# MotorBoard.net
KiCad netlist of a schematic drawn in EAGLE
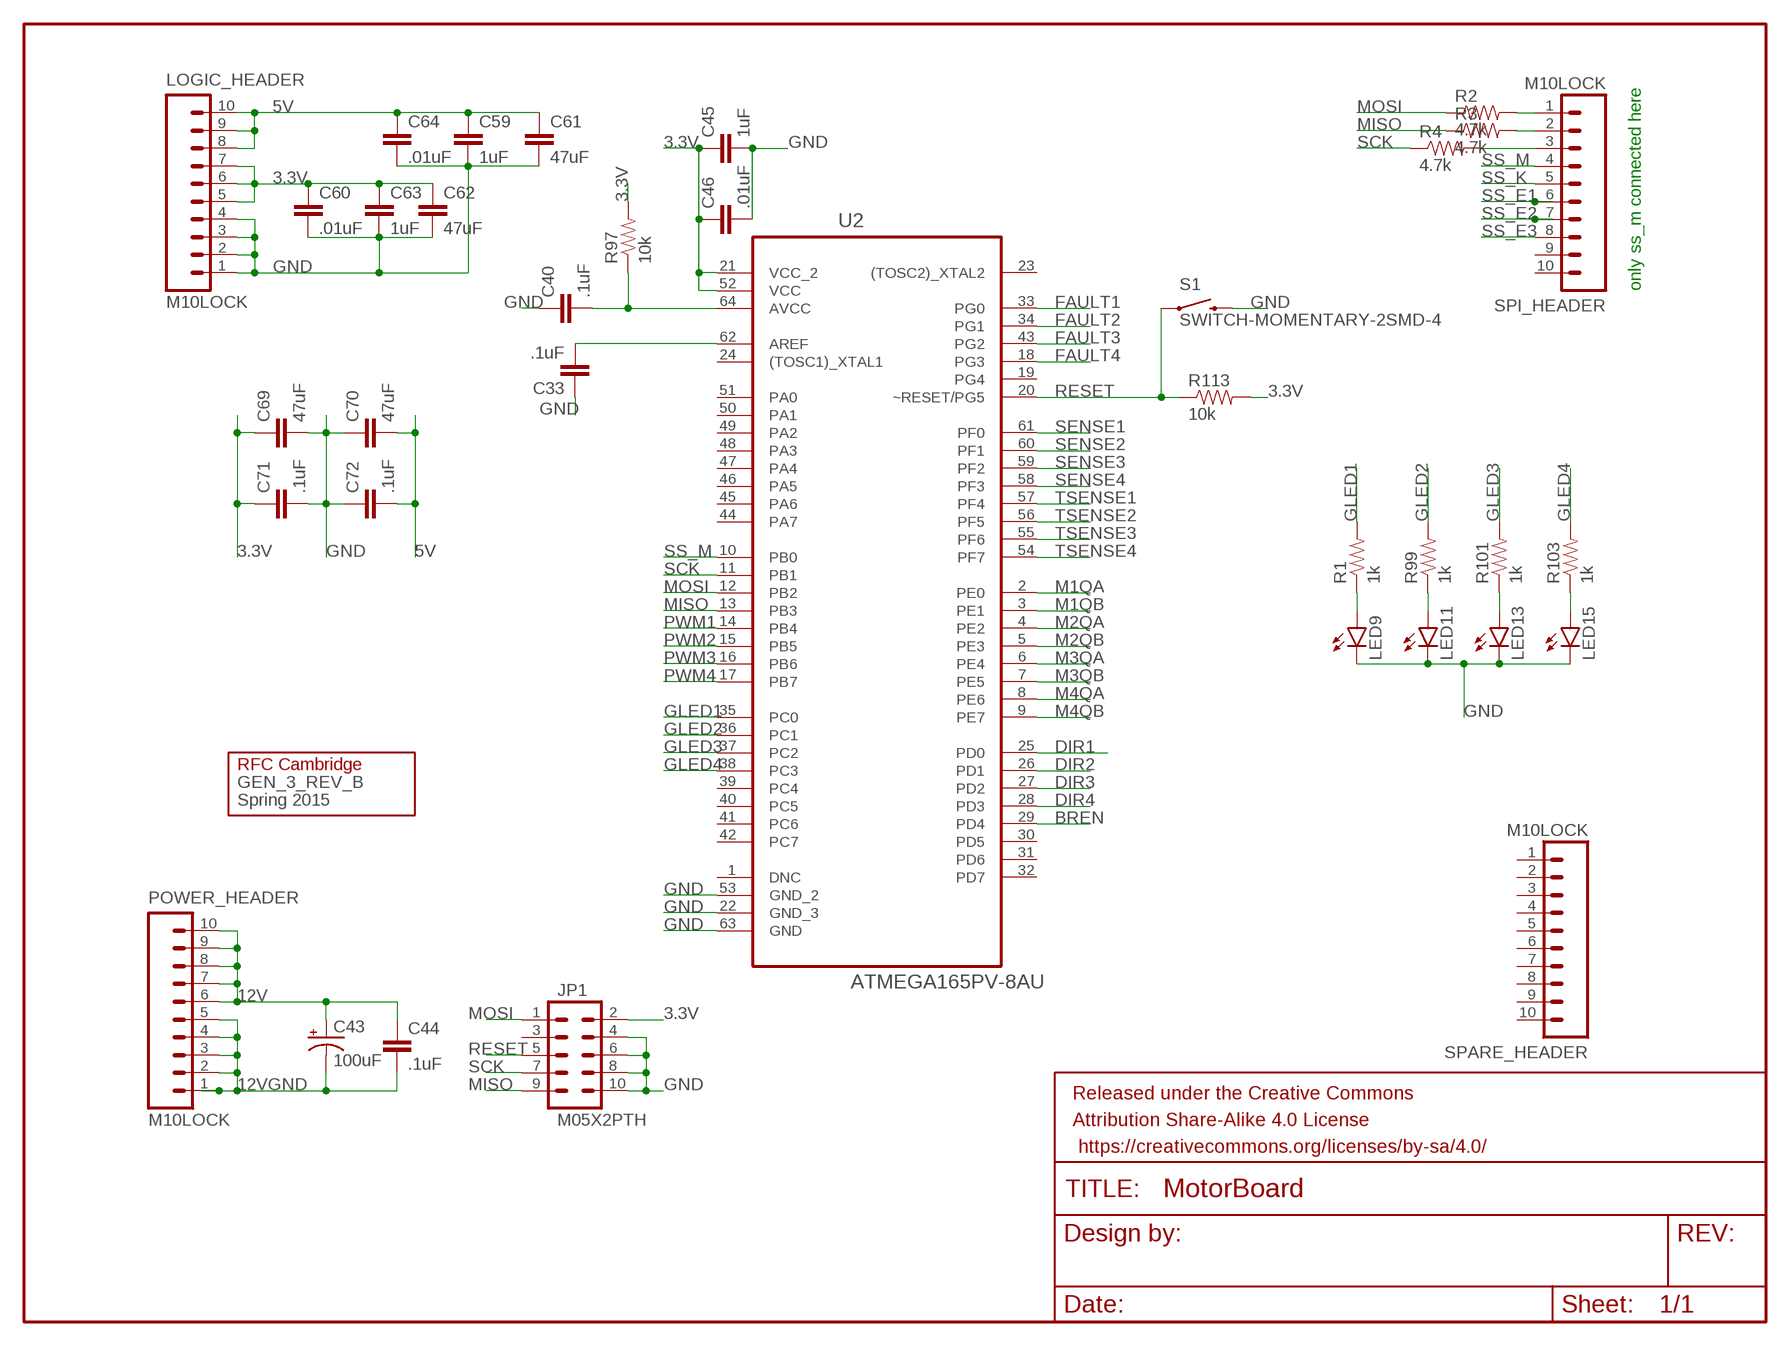
[diagram p0: schematic, sheet 1, part 1 of 2]
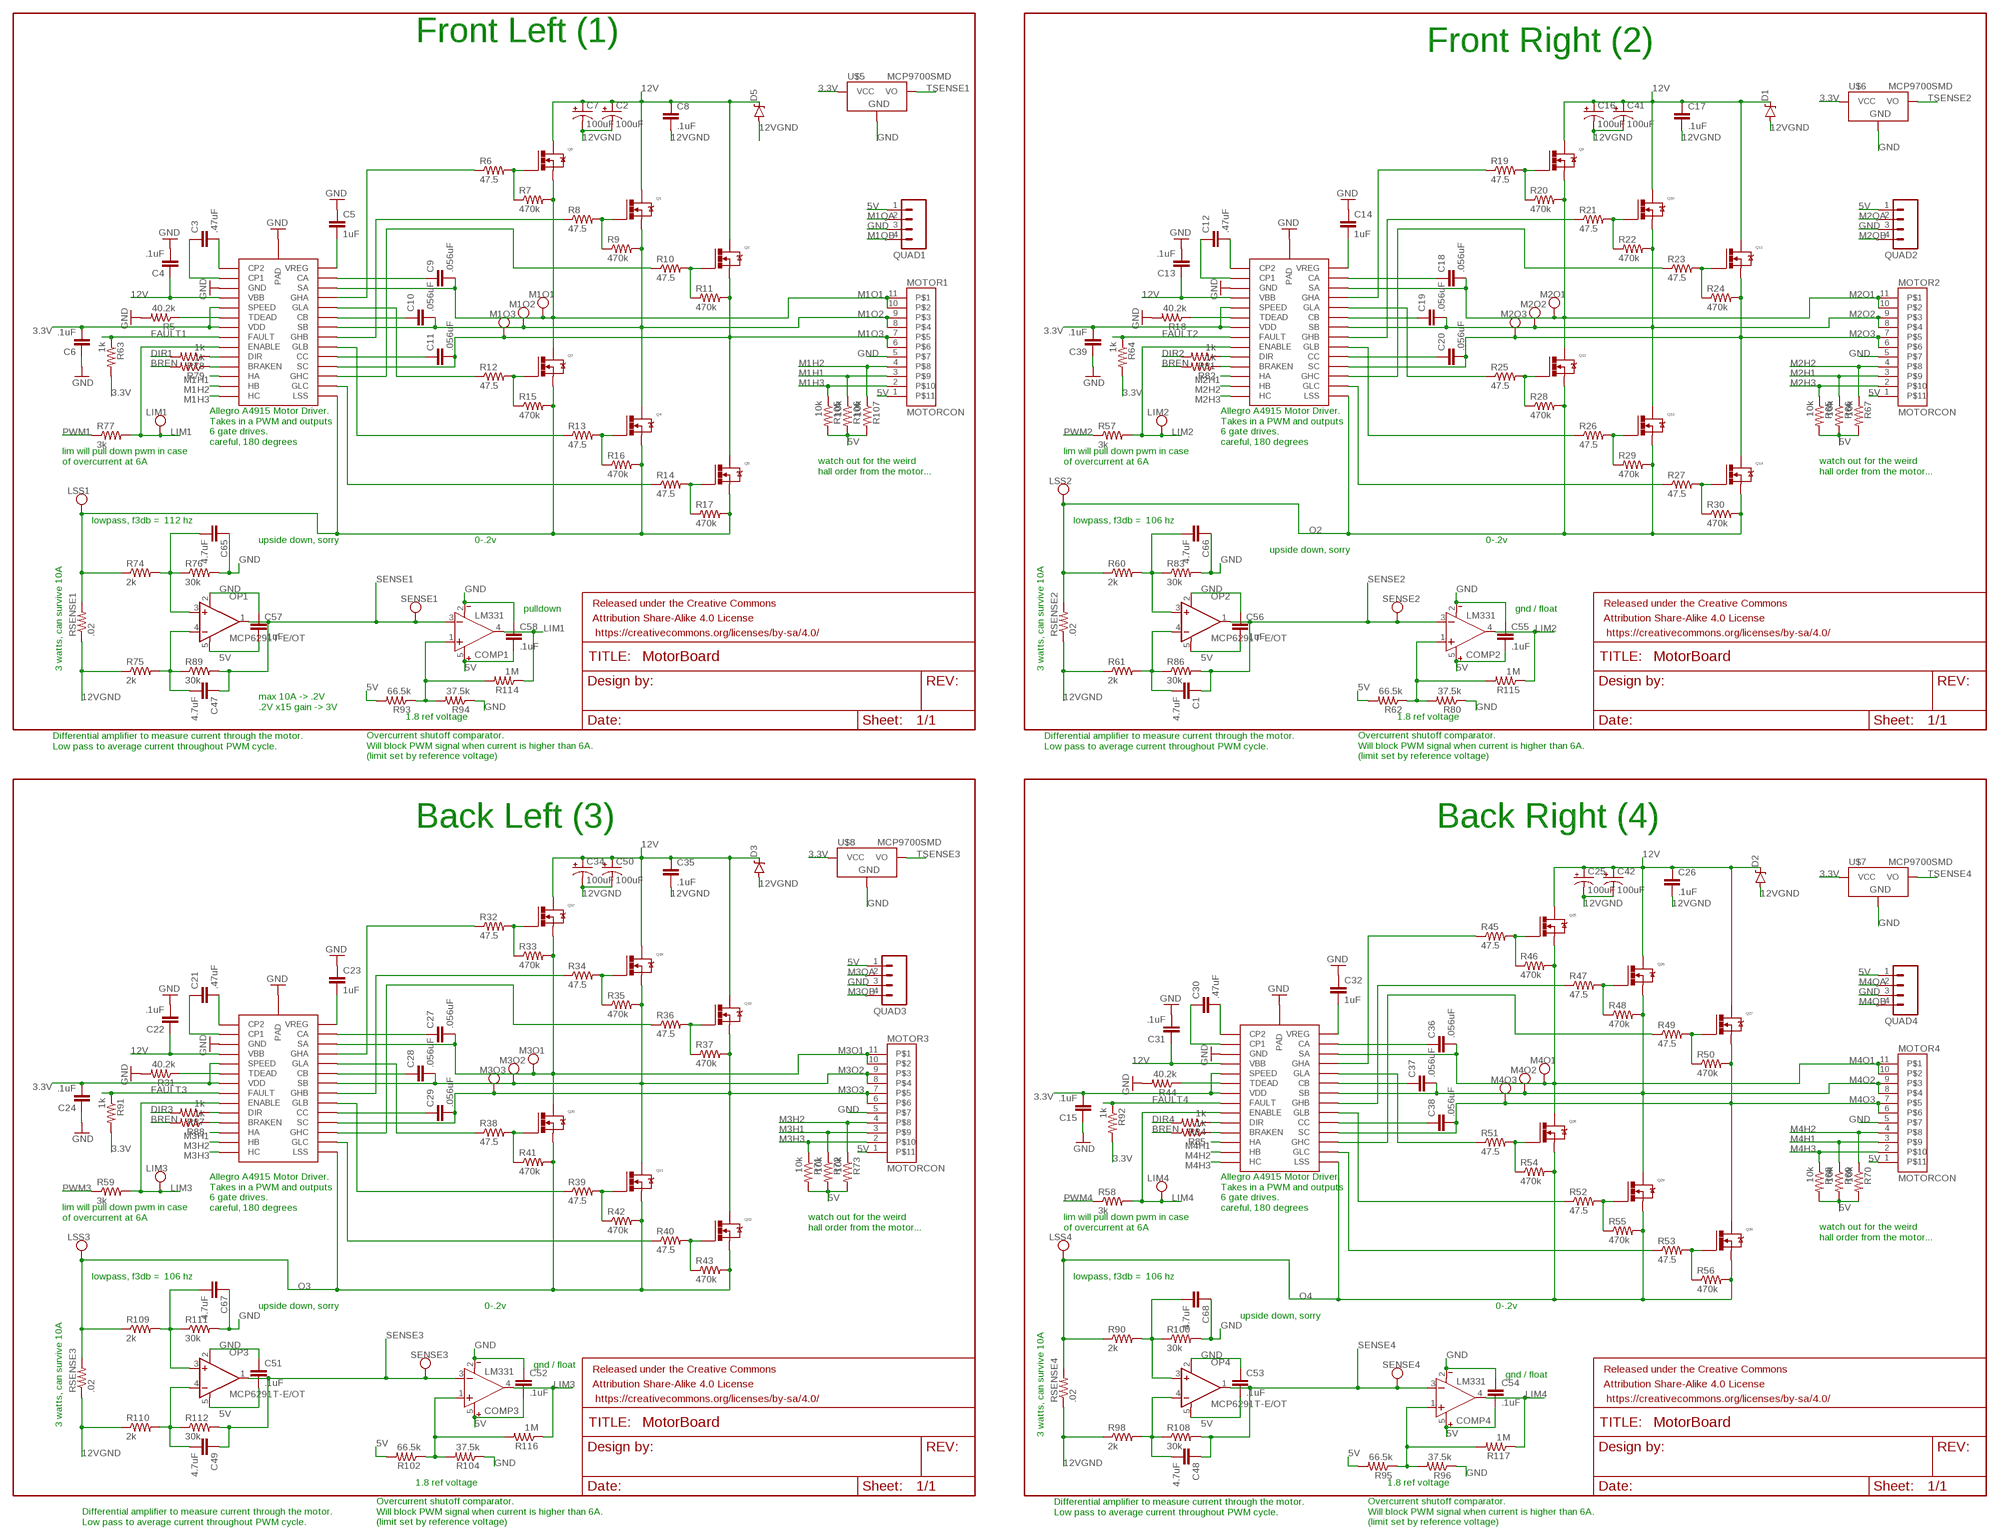
[diagram p1: schematic, sheet 1, part 2 of 2]

(export (version "E")
  (design (tool "Eeschema 10.0.6"))
  (components
    (comp (ref "C1")
      (value "4.7uF")
      (footprint "eagle-import:0805")
      (libsource (lib "eagle-import") (part "SparkFun-Passives_CAP0805"))
    )
    (comp (ref "C2")
      (value "100uF")
      (footprint "eagle-import:PANASONIC_D")
      (libsource (lib "eagle-import") (part "CAP-POLAR"))
    )
    (comp (ref "C3")
      (value ".47uF")
      (footprint "eagle-import:0805")
      (libsource (lib "eagle-import") (part "SparkFun-Passives_CAP0805"))
    )
    (comp (ref "C4")
      (value ".1uF")
      (footprint "eagle-import:0805")
      (libsource (lib "eagle-import") (part "SparkFun-Passives_CAP0805"))
    )
    (comp (ref "C5")
      (value "1uF")
      (footprint "eagle-import:0805")
      (libsource (lib "eagle-import") (part "SparkFun-Passives_CAP0805"))
    )
    (comp (ref "C6")
      (value ".1uF")
      (footprint "eagle-import:0805")
      (libsource (lib "eagle-import") (part "SparkFun-Passives_CAP0805"))
    )
    (comp (ref "C7")
      (value "100uF")
      (footprint "eagle-import:PANASONIC_D")
      (libsource (lib "eagle-import") (part "CAP-POLAR"))
    )
    (comp (ref "C8")
      (value ".1uF")
      (footprint "eagle-import:0805")
      (libsource (lib "eagle-import") (part "SparkFun-Passives_CAP0805"))
    )
    (comp (ref "C9")
      (value ".056uF")
      (footprint "eagle-import:0805")
      (libsource (lib "eagle-import") (part "SparkFun-Passives_CAP0805"))
    )
    (comp (ref "C10")
      (value ".056uF")
      (footprint "eagle-import:0805")
      (libsource (lib "eagle-import") (part "SparkFun-Passives_CAP0805"))
    )
    (comp (ref "C11")
      (value ".056uF")
      (footprint "eagle-import:0805")
      (libsource (lib "eagle-import") (part "SparkFun-Passives_CAP0805"))
    )
    (comp (ref "C12")
      (value ".47uF")
      (footprint "eagle-import:0805")
      (libsource (lib "eagle-import") (part "SparkFun-Passives_CAP0805"))
    )
    (comp (ref "C13")
      (value ".1uF")
      (footprint "eagle-import:0805")
      (libsource (lib "eagle-import") (part "SparkFun-Passives_CAP0805"))
    )
    (comp (ref "C14")
      (value "1uF")
      (footprint "eagle-import:0805")
      (libsource (lib "eagle-import") (part "SparkFun-Passives_CAP0805"))
    )
    (comp (ref "C15")
      (value ".1uF")
      (footprint "eagle-import:0805")
      (libsource (lib "eagle-import") (part "SparkFun-Passives_CAP0805"))
    )
    (comp (ref "C16")
      (value "100uF")
      (footprint "eagle-import:PANASONIC_D")
      (libsource (lib "eagle-import") (part "CAP-POLAR"))
    )
    (comp (ref "C17")
      (value ".1uF")
      (footprint "eagle-import:0805")
      (libsource (lib "eagle-import") (part "SparkFun-Passives_CAP0805"))
    )
    (comp (ref "C18")
      (value ".056uF")
      (footprint "eagle-import:0805")
      (libsource (lib "eagle-import") (part "SparkFun-Passives_CAP0805"))
    )
    (comp (ref "C19")
      (value ".056uF")
      (footprint "eagle-import:0805")
      (libsource (lib "eagle-import") (part "SparkFun-Passives_CAP0805"))
    )
    (comp (ref "C20")
      (value ".056uF")
      (footprint "eagle-import:0805")
      (libsource (lib "eagle-import") (part "SparkFun-Passives_CAP0805"))
    )
    (comp (ref "C21")
      (value ".47uF")
      (footprint "eagle-import:0805")
      (libsource (lib "eagle-import") (part "SparkFun-Passives_CAP0805"))
    )
    (comp (ref "C22")
      (value ".1uF")
      (footprint "eagle-import:0805")
      (libsource (lib "eagle-import") (part "SparkFun-Passives_CAP0805"))
    )
    (comp (ref "C23")
      (value "1uF")
      (footprint "eagle-import:0805")
      (libsource (lib "eagle-import") (part "SparkFun-Passives_CAP0805"))
    )
    (comp (ref "C24")
      (value ".1uF")
      (footprint "eagle-import:0805")
      (libsource (lib "eagle-import") (part "SparkFun-Passives_CAP0805"))
    )
    (comp (ref "C25")
      (value "100uF")
      (footprint "eagle-import:PANASONIC_D")
      (libsource (lib "eagle-import") (part "CAP-POLAR"))
    )
    (comp (ref "C26")
      (value ".1uF")
      (footprint "eagle-import:0805")
      (libsource (lib "eagle-import") (part "SparkFun-Passives_CAP0805"))
    )
    (comp (ref "C27")
      (value ".056uF")
      (footprint "eagle-import:0805")
      (libsource (lib "eagle-import") (part "SparkFun-Passives_CAP0805"))
    )
    (comp (ref "C28")
      (value ".056uF")
      (footprint "eagle-import:0805")
      (libsource (lib "eagle-import") (part "SparkFun-Passives_CAP0805"))
    )
    (comp (ref "C29")
      (value ".056uF")
      (footprint "eagle-import:0805")
      (libsource (lib "eagle-import") (part "SparkFun-Passives_CAP0805"))
    )
    (comp (ref "C30")
      (value ".47uF")
      (footprint "eagle-import:0805")
      (libsource (lib "eagle-import") (part "SparkFun-Passives_CAP0805"))
    )
    (comp (ref "C31")
      (value ".1uF")
      (footprint "eagle-import:0805")
      (libsource (lib "eagle-import") (part "SparkFun-Passives_CAP0805"))
    )
    (comp (ref "C32")
      (value "1uF")
      (footprint "eagle-import:0805")
      (libsource (lib "eagle-import") (part "SparkFun-Passives_CAP0805"))
    )
    (comp (ref "C33")
      (value ".1uF")
      (footprint "eagle-import:0805")
      (libsource (lib "eagle-import") (part "CAP0805"))
    )
    (comp (ref "C34")
      (value "100uF")
      (footprint "eagle-import:PANASONIC_D")
      (libsource (lib "eagle-import") (part "CAP-POLAR"))
    )
    (comp (ref "C35")
      (value ".1uF")
      (footprint "eagle-import:0805")
      (libsource (lib "eagle-import") (part "SparkFun-Passives_CAP0805"))
    )
    (comp (ref "C36")
      (value ".056uF")
      (footprint "eagle-import:0805")
      (libsource (lib "eagle-import") (part "SparkFun-Passives_CAP0805"))
    )
    (comp (ref "C37")
      (value ".056uF")
      (footprint "eagle-import:0805")
      (libsource (lib "eagle-import") (part "SparkFun-Passives_CAP0805"))
    )
    (comp (ref "C38")
      (value ".056uF")
      (footprint "eagle-import:0805")
      (libsource (lib "eagle-import") (part "SparkFun-Passives_CAP0805"))
    )
    (comp (ref "C39")
      (value ".1uF")
      (footprint "eagle-import:0805")
      (libsource (lib "eagle-import") (part "SparkFun-Passives_CAP0805"))
    )
    (comp (ref "C40")
      (value ".1uF")
      (footprint "eagle-import:0805")
      (libsource (lib "eagle-import") (part "CAP0805"))
    )
    (comp (ref "C41")
      (value "100uF")
      (footprint "eagle-import:PANASONIC_D")
      (libsource (lib "eagle-import") (part "CAP-POLAR"))
    )
    (comp (ref "C42")
      (value "100uF")
      (footprint "eagle-import:PANASONIC_D")
      (libsource (lib "eagle-import") (part "CAP-POLAR"))
    )
    (comp (ref "C43")
      (value "100uF")
      (footprint "eagle-import:PANASONIC_D")
      (libsource (lib "eagle-import") (part "CAP-POLAR"))
    )
    (comp (ref "C44")
      (value ".1uF")
      (footprint "eagle-import:0805")
      (libsource (lib "eagle-import") (part "SparkFun-Passives_CAP0805"))
    )
    (comp (ref "C45")
      (value "1uF")
      (footprint "eagle-import:0805")
      (libsource (lib "eagle-import") (part "CAP0805"))
    )
    (comp (ref "C46")
      (value ".01uF")
      (footprint "eagle-import:0805")
      (libsource (lib "eagle-import") (part "CAP0805"))
    )
    (comp (ref "C47")
      (value "4.7uF")
      (footprint "eagle-import:0805")
      (libsource (lib "eagle-import") (part "SparkFun-Passives_CAP0805"))
    )
    (comp (ref "C48")
      (value "4.7uF")
      (footprint "eagle-import:0805")
      (libsource (lib "eagle-import") (part "SparkFun-Passives_CAP0805"))
    )
    (comp (ref "C49")
      (value "4.7uF")
      (footprint "eagle-import:0805")
      (libsource (lib "eagle-import") (part "SparkFun-Passives_CAP0805"))
    )
    (comp (ref "C50")
      (value "100uF")
      (footprint "eagle-import:PANASONIC_D")
      (libsource (lib "eagle-import") (part "CAP-POLAR"))
    )
    (comp (ref "C51")
      (value ".1uF")
      (footprint "eagle-import:0805")
      (libsource (lib "eagle-import") (part "SparkFun-Passives_CAP0805"))
    )
    (comp (ref "C52")
      (value ".1uF")
      (footprint "eagle-import:0805")
      (libsource (lib "eagle-import") (part "SparkFun-Passives_CAP0805"))
    )
    (comp (ref "C53")
      (value ".1uF")
      (footprint "eagle-import:0805")
      (libsource (lib "eagle-import") (part "SparkFun-Passives_CAP0805"))
    )
    (comp (ref "C54")
      (value ".1uF")
      (footprint "eagle-import:0805")
      (libsource (lib "eagle-import") (part "SparkFun-Passives_CAP0805"))
    )
    (comp (ref "C55")
      (value ".1uF")
      (footprint "eagle-import:0805")
      (libsource (lib "eagle-import") (part "SparkFun-Passives_CAP0805"))
    )
    (comp (ref "C56")
      (value ".1uF")
      (footprint "eagle-import:0805")
      (libsource (lib "eagle-import") (part "SparkFun-Passives_CAP0805"))
    )
    (comp (ref "C57")
      (value ".1uF")
      (footprint "eagle-import:0805")
      (libsource (lib "eagle-import") (part "SparkFun-Passives_CAP0805"))
    )
    (comp (ref "C58")
      (value ".1uF")
      (footprint "eagle-import:0805")
      (libsource (lib "eagle-import") (part "SparkFun-Passives_CAP0805"))
    )
    (comp (ref "C59")
      (value "1uF")
      (footprint "eagle-import:0805")
      (libsource (lib "eagle-import") (part "CAP0805"))
    )
    (comp (ref "C60")
      (value ".01uF")
      (footprint "eagle-import:0805")
      (libsource (lib "eagle-import") (part "CAP0805"))
    )
    (comp (ref "C61")
      (value "47uF")
      (footprint "eagle-import:1206")
      (libsource (lib "eagle-import") (part "CAP1206"))
    )
    (comp (ref "C62")
      (value "47uF")
      (footprint "eagle-import:1206")
      (libsource (lib "eagle-import") (part "CAP1206"))
    )
    (comp (ref "C63")
      (value "1uF")
      (footprint "eagle-import:0805")
      (libsource (lib "eagle-import") (part "CAP0805"))
    )
    (comp (ref "C64")
      (value ".01uF")
      (footprint "eagle-import:0805")
      (libsource (lib "eagle-import") (part "CAP0805"))
    )
    (comp (ref "C65")
      (value "4.7uF")
      (footprint "eagle-import:0805")
      (libsource (lib "eagle-import") (part "SparkFun-Passives_CAP0805"))
    )
    (comp (ref "C66")
      (value "4.7uF")
      (footprint "eagle-import:0805")
      (libsource (lib "eagle-import") (part "SparkFun-Passives_CAP0805"))
    )
    (comp (ref "C67")
      (value "4.7uF")
      (footprint "eagle-import:0805")
      (libsource (lib "eagle-import") (part "SparkFun-Passives_CAP0805"))
    )
    (comp (ref "C68")
      (value "4.7uF")
      (footprint "eagle-import:0805")
      (libsource (lib "eagle-import") (part "SparkFun-Passives_CAP0805"))
    )
    (comp (ref "C69")
      (value "47uF")
      (footprint "eagle-import:1206")
      (libsource (lib "eagle-import") (part "CAP1206"))
    )
    (comp (ref "C70")
      (value "47uF")
      (footprint "eagle-import:1206")
      (libsource (lib "eagle-import") (part "CAP1206"))
    )
    (comp (ref "C71")
      (value ".1uF")
      (footprint "eagle-import:0805")
      (libsource (lib "eagle-import") (part "CAP0805"))
    )
    (comp (ref "C72")
      (value ".1uF")
      (footprint "eagle-import:0805")
      (libsource (lib "eagle-import") (part "CAP0805"))
    )
    (comp (ref "COMP1")
      (value "LM331")
      (footprint "eagle-import:SOT23-5")
      (libsource (lib "eagle-import") (part "LM331"))
    )
    (comp (ref "COMP2")
      (value "LM331")
      (footprint "eagle-import:SOT23-5")
      (libsource (lib "eagle-import") (part "LM331"))
    )
    (comp (ref "COMP3")
      (value "LM331")
      (footprint "eagle-import:SOT23-5")
      (libsource (lib "eagle-import") (part "LM331"))
    )
    (comp (ref "COMP4")
      (value "LM331")
      (footprint "eagle-import:SOT23-5")
      (libsource (lib "eagle-import") (part "LM331"))
    )
    (comp (ref "D1")
      (value "DIODE-ZENERDO214AC")
      (footprint "eagle-import:DO214AC")
      (libsource (lib "eagle-import") (part "DIODE-ZENERDO214AC"))
    )
    (comp (ref "D2")
      (value "DIODE-ZENERDO214AC")
      (footprint "eagle-import:DO214AC")
      (libsource (lib "eagle-import") (part "DIODE-ZENERDO214AC"))
    )
    (comp (ref "D3")
      (value "DIODE-ZENERDO214AC")
      (footprint "eagle-import:DO214AC")
      (libsource (lib "eagle-import") (part "DIODE-ZENERDO214AC"))
    )
    (comp (ref "D5")
      (value "DIODE-ZENERDO214AC")
      (footprint "eagle-import:DO214AC")
      (libsource (lib "eagle-import") (part "DIODE-ZENERDO214AC"))
    )
    (comp (ref "FRAME1")
      (value "FRAME-LETTER")
      (footprint "eagle-import:CREATIVE_COMMONS")
      (libsource (lib "eagle-import") (part "FRAME-LETTER"))
    )
    (comp (ref "FRAME2")
      (value "FRAME-LETTER")
      (footprint "eagle-import:CREATIVE_COMMONS")
      (libsource (lib "eagle-import") (part "FRAME-LETTER"))
    )
    (comp (ref "FRAME5")
      (value "FRAME-LETTER")
      (footprint "eagle-import:CREATIVE_COMMONS")
      (libsource (lib "eagle-import") (part "FRAME-LETTER"))
    )
    (comp (ref "FRAME6")
      (value "FRAME-LETTER")
      (footprint "eagle-import:CREATIVE_COMMONS")
      (libsource (lib "eagle-import") (part "FRAME-LETTER"))
    )
    (comp (ref "FRAME7")
      (value "FRAME-LETTER")
      (footprint "eagle-import:CREATIVE_COMMONS")
      (libsource (lib "eagle-import") (part "FRAME-LETTER"))
    )
    (comp (ref "GEN_3_REV_B")
      (value "Spring 2015")
      (footprint "eagle-import:LOGO")
      (libsource (lib "eagle-import") (part "LOGO"))
    )
    (comp (ref "JP1")
      (value "M05X2PTH")
      (footprint "eagle-import:AVR_ICSP")
      (libsource (lib "eagle-import") (part "M05X2PTH"))
    )
    (comp (ref "LED9")
      (value "LED1206")
      (footprint "eagle-import:LED-1206")
      (libsource (lib "eagle-import") (part "LED1206"))
    )
    (comp (ref "LED11")
      (value "LED1206")
      (footprint "eagle-import:LED-1206")
      (libsource (lib "eagle-import") (part "LED1206"))
    )
    (comp (ref "LED13")
      (value "LED1206")
      (footprint "eagle-import:LED-1206")
      (libsource (lib "eagle-import") (part "LED1206"))
    )
    (comp (ref "LED15")
      (value "LED1206")
      (footprint "eagle-import:LED-1206")
      (libsource (lib "eagle-import") (part "LED1206"))
    )
    (comp (ref "LIM1")
      (value "TEST_PT")
      (footprint "eagle-import:TESTING_PT")
      (libsource (lib "eagle-import") (part "TEST_PT"))
    )
    (comp (ref "LIM2")
      (value "TEST_PT")
      (footprint "eagle-import:TESTING_PT")
      (libsource (lib "eagle-import") (part "TEST_PT"))
    )
    (comp (ref "LIM3")
      (value "TEST_PT")
      (footprint "eagle-import:TESTING_PT")
      (libsource (lib "eagle-import") (part "TEST_PT"))
    )
    (comp (ref "LIM4")
      (value "TEST_PT")
      (footprint "eagle-import:TESTING_PT")
      (libsource (lib "eagle-import") (part "TEST_PT"))
    )
    (comp (ref "LOGIC_HEADER")
      (value "M10LOCK")
      (footprint "eagle-import:1X10_LOCK")
      (libsource (lib "eagle-import") (part "M10LOCK"))
    )
    (comp (ref "LSS1")
      (value "TEST_PT")
      (footprint "eagle-import:TESTING_PT")
      (libsource (lib "eagle-import") (part "TEST_PT"))
    )
    (comp (ref "LSS2")
      (value "TEST_PT")
      (footprint "eagle-import:TESTING_PT")
      (libsource (lib "eagle-import") (part "TEST_PT"))
    )
    (comp (ref "LSS3")
      (value "TEST_PT")
      (footprint "eagle-import:TESTING_PT")
      (libsource (lib "eagle-import") (part "TEST_PT"))
    )
    (comp (ref "LSS4")
      (value "TEST_PT")
      (footprint "eagle-import:TESTING_PT")
      (libsource (lib "eagle-import") (part "TEST_PT"))
    )
    (comp (ref "M1O1")
      (value "TEST_PT")
      (footprint "eagle-import:TESTING_PT")
      (libsource (lib "eagle-import") (part "TEST_PT"))
    )
    (comp (ref "M1O2")
      (value "TEST_PT")
      (footprint "eagle-import:TESTING_PT")
      (libsource (lib "eagle-import") (part "TEST_PT"))
    )
    (comp (ref "M1O3")
      (value "TEST_PT")
      (footprint "eagle-import:TESTING_PT")
      (libsource (lib "eagle-import") (part "TEST_PT"))
    )
    (comp (ref "M2O1")
      (value "TEST_PT")
      (footprint "eagle-import:TESTING_PT")
      (libsource (lib "eagle-import") (part "TEST_PT"))
    )
    (comp (ref "M2O2")
      (value "TEST_PT")
      (footprint "eagle-import:TESTING_PT")
      (libsource (lib "eagle-import") (part "TEST_PT"))
    )
    (comp (ref "M2O3")
      (value "TEST_PT")
      (footprint "eagle-import:TESTING_PT")
      (libsource (lib "eagle-import") (part "TEST_PT"))
    )
    (comp (ref "M3O1")
      (value "TEST_PT")
      (footprint "eagle-import:TESTING_PT")
      (libsource (lib "eagle-import") (part "TEST_PT"))
    )
    (comp (ref "M3O2")
      (value "TEST_PT")
      (footprint "eagle-import:TESTING_PT")
      (libsource (lib "eagle-import") (part "TEST_PT"))
    )
    (comp (ref "M3O3")
      (value "TEST_PT")
      (footprint "eagle-import:TESTING_PT")
      (libsource (lib "eagle-import") (part "TEST_PT"))
    )
    (comp (ref "M4O1")
      (value "TEST_PT")
      (footprint "eagle-import:TESTING_PT")
      (libsource (lib "eagle-import") (part "TEST_PT"))
    )
    (comp (ref "M4O2")
      (value "TEST_PT")
      (footprint "eagle-import:TESTING_PT")
      (libsource (lib "eagle-import") (part "TEST_PT"))
    )
    (comp (ref "M4O3")
      (value "TEST_PT")
      (footprint "eagle-import:TESTING_PT")
      (libsource (lib "eagle-import") (part "TEST_PT"))
    )
    (comp (ref "MOTOR1")
      (value "MOTORCON")
      (footprint "eagle-import:GEN3CON")
      (libsource (lib "eagle-import") (part "MOTORCON"))
    )
    (comp (ref "MOTOR2")
      (value "MOTORCON")
      (footprint "eagle-import:GEN3CON")
      (libsource (lib "eagle-import") (part "MOTORCON"))
    )
    (comp (ref "MOTOR3")
      (value "MOTORCON")
      (footprint "eagle-import:GEN3CON")
      (libsource (lib "eagle-import") (part "MOTORCON"))
    )
    (comp (ref "MOTOR4")
      (value "MOTORCON")
      (footprint "eagle-import:GEN3CON")
      (libsource (lib "eagle-import") (part "MOTORCON"))
    )
    (comp (ref "OP1")
      (value "MCP6291T-E/OT")
      (footprint "eagle-import:SOT23-5")
      (libsource (lib "eagle-import") (part "MCP6291T-E/OT"))
    )
    (comp (ref "OP2")
      (value "MCP6291T-E/OT")
      (footprint "eagle-import:SOT23-5")
      (libsource (lib "eagle-import") (part "MCP6291T-E/OT"))
    )
    (comp (ref "OP3")
      (value "MCP6291T-E/OT")
      (footprint "eagle-import:SOT23-5")
      (libsource (lib "eagle-import") (part "MCP6291T-E/OT"))
    )
    (comp (ref "OP4")
      (value "MCP6291T-E/OT")
      (footprint "eagle-import:SOT23-5")
      (libsource (lib "eagle-import") (part "MCP6291T-E/OT"))
    )
    (comp (ref "POWER_HEADER")
      (value "M10LOCK")
      (footprint "eagle-import:1X10_LOCK")
      (libsource (lib "eagle-import") (part "M10LOCK"))
    )
    (comp (ref "Q1")
      (value "N-MOSFET")
      (footprint "eagle-import:DPAK")
      (libsource (lib "eagle-import") (part "N-MOSFET"))
    )
    (comp (ref "Q2")
      (value "N-MOSFET")
      (footprint "eagle-import:DPAK")
      (libsource (lib "eagle-import") (part "N-MOSFET"))
    )
    (comp (ref "Q3")
      (value "N-MOSFET")
      (footprint "eagle-import:DPAK")
      (libsource (lib "eagle-import") (part "N-MOSFET"))
    )
    (comp (ref "Q4")
      (value "N-MOSFET")
      (footprint "eagle-import:DPAK")
      (libsource (lib "eagle-import") (part "N-MOSFET"))
    )
    (comp (ref "Q5")
      (value "N-MOSFET")
      (footprint "eagle-import:DPAK")
      (libsource (lib "eagle-import") (part "N-MOSFET"))
    )
    (comp (ref "Q6")
      (value "N-MOSFET")
      (footprint "eagle-import:DPAK")
      (libsource (lib "eagle-import") (part "N-MOSFET"))
    )
    (comp (ref "Q9")
      (value "N-MOSFET")
      (footprint "eagle-import:DPAK")
      (libsource (lib "eagle-import") (part "N-MOSFET"))
    )
    (comp (ref "Q10")
      (value "N-MOSFET")
      (footprint "eagle-import:DPAK")
      (libsource (lib "eagle-import") (part "N-MOSFET"))
    )
    (comp (ref "Q11")
      (value "N-MOSFET")
      (footprint "eagle-import:DPAK")
      (libsource (lib "eagle-import") (part "N-MOSFET"))
    )
    (comp (ref "Q12")
      (value "N-MOSFET")
      (footprint "eagle-import:DPAK")
      (libsource (lib "eagle-import") (part "N-MOSFET"))
    )
    (comp (ref "Q13")
      (value "N-MOSFET")
      (footprint "eagle-import:DPAK")
      (libsource (lib "eagle-import") (part "N-MOSFET"))
    )
    (comp (ref "Q14")
      (value "N-MOSFET")
      (footprint "eagle-import:DPAK")
      (libsource (lib "eagle-import") (part "N-MOSFET"))
    )
    (comp (ref "Q17")
      (value "N-MOSFET")
      (footprint "eagle-import:DPAK")
      (libsource (lib "eagle-import") (part "N-MOSFET"))
    )
    (comp (ref "Q18")
      (value "N-MOSFET")
      (footprint "eagle-import:DPAK")
      (libsource (lib "eagle-import") (part "N-MOSFET"))
    )
    (comp (ref "Q19")
      (value "N-MOSFET")
      (footprint "eagle-import:DPAK")
      (libsource (lib "eagle-import") (part "N-MOSFET"))
    )
    (comp (ref "Q20")
      (value "N-MOSFET")
      (footprint "eagle-import:DPAK")
      (libsource (lib "eagle-import") (part "N-MOSFET"))
    )
    (comp (ref "Q21")
      (value "N-MOSFET")
      (footprint "eagle-import:DPAK")
      (libsource (lib "eagle-import") (part "N-MOSFET"))
    )
    (comp (ref "Q22")
      (value "N-MOSFET")
      (footprint "eagle-import:DPAK")
      (libsource (lib "eagle-import") (part "N-MOSFET"))
    )
    (comp (ref "Q25")
      (value "N-MOSFET")
      (footprint "eagle-import:DPAK")
      (libsource (lib "eagle-import") (part "N-MOSFET"))
    )
    (comp (ref "Q26")
      (value "N-MOSFET")
      (footprint "eagle-import:DPAK")
      (libsource (lib "eagle-import") (part "N-MOSFET"))
    )
    (comp (ref "Q27")
      (value "N-MOSFET")
      (footprint "eagle-import:DPAK")
      (libsource (lib "eagle-import") (part "N-MOSFET"))
    )
    (comp (ref "Q28")
      (value "N-MOSFET")
      (footprint "eagle-import:DPAK")
      (libsource (lib "eagle-import") (part "N-MOSFET"))
    )
    (comp (ref "Q29")
      (value "N-MOSFET")
      (footprint "eagle-import:DPAK")
      (libsource (lib "eagle-import") (part "N-MOSFET"))
    )
    (comp (ref "Q30")
      (value "N-MOSFET")
      (footprint "eagle-import:DPAK")
      (libsource (lib "eagle-import") (part "N-MOSFET"))
    )
    (comp (ref "QUAD1")
      (value "M04LOCK")
      (footprint "eagle-import:1X04_LOCK")
      (libsource (lib "eagle-import") (part "M04LOCK"))
    )
    (comp (ref "QUAD2")
      (value "M04LOCK")
      (footprint "eagle-import:1X04_LOCK")
      (libsource (lib "eagle-import") (part "M04LOCK"))
    )
    (comp (ref "QUAD3")
      (value "M04LOCK")
      (footprint "eagle-import:1X04_LOCK")
      (libsource (lib "eagle-import") (part "M04LOCK"))
    )
    (comp (ref "QUAD4")
      (value "M04LOCK")
      (footprint "eagle-import:1X04_LOCK")
      (libsource (lib "eagle-import") (part "M04LOCK"))
    )
    (comp (ref "R1")
      (value "1k")
      (footprint "eagle-import:0805")
      (libsource (lib "eagle-import") (part "RESISTOR0805-RES"))
    )
    (comp (ref "R2")
      (value "4.7k")
      (footprint "eagle-import:0805")
      (libsource (lib "eagle-import") (part "RESISTOR0805-RES"))
    )
    (comp (ref "R3")
      (value "4.7k")
      (footprint "eagle-import:0805")
      (libsource (lib "eagle-import") (part "RESISTOR0805-RES"))
    )
    (comp (ref "R4")
      (value "4.7k")
      (footprint "eagle-import:0805")
      (libsource (lib "eagle-import") (part "RESISTOR0805-RES"))
    )
    (comp (ref "R5")
      (value "40.2k")
      (footprint "eagle-import:0805")
      (libsource (lib "eagle-import") (part "SparkFun-Resistors_RESISTOR0805-RES"))
    )
    (comp (ref "R6")
      (value "47.5")
      (footprint "eagle-import:0805")
      (libsource (lib "eagle-import") (part "SparkFun-Resistors_RESISTOR0805-RES"))
    )
    (comp (ref "R7")
      (value "470k")
      (footprint "eagle-import:0805")
      (libsource (lib "eagle-import") (part "SparkFun-Resistors_RESISTOR0805-RES"))
    )
    (comp (ref "R8")
      (value "47.5")
      (footprint "eagle-import:0805")
      (libsource (lib "eagle-import") (part "SparkFun-Resistors_RESISTOR0805-RES"))
    )
    (comp (ref "R9")
      (value "470k")
      (footprint "eagle-import:0805")
      (libsource (lib "eagle-import") (part "SparkFun-Resistors_RESISTOR0805-RES"))
    )
    (comp (ref "R10")
      (value "47.5")
      (footprint "eagle-import:0805")
      (libsource (lib "eagle-import") (part "SparkFun-Resistors_RESISTOR0805-RES"))
    )
    (comp (ref "R11")
      (value "470k")
      (footprint "eagle-import:0805")
      (libsource (lib "eagle-import") (part "SparkFun-Resistors_RESISTOR0805-RES"))
    )
    (comp (ref "R12")
      (value "47.5")
      (footprint "eagle-import:0805")
      (libsource (lib "eagle-import") (part "SparkFun-Resistors_RESISTOR0805-RES"))
    )
    (comp (ref "R13")
      (value "47.5")
      (footprint "eagle-import:0805")
      (libsource (lib "eagle-import") (part "SparkFun-Resistors_RESISTOR0805-RES"))
    )
    (comp (ref "R14")
      (value "47.5")
      (footprint "eagle-import:0805")
      (libsource (lib "eagle-import") (part "SparkFun-Resistors_RESISTOR0805-RES"))
    )
    (comp (ref "R15")
      (value "470k")
      (footprint "eagle-import:0805")
      (libsource (lib "eagle-import") (part "SparkFun-Resistors_RESISTOR0805-RES"))
    )
    (comp (ref "R16")
      (value "470k")
      (footprint "eagle-import:0805")
      (libsource (lib "eagle-import") (part "SparkFun-Resistors_RESISTOR0805-RES"))
    )
    (comp (ref "R17")
      (value "470k")
      (footprint "eagle-import:0805")
      (libsource (lib "eagle-import") (part "SparkFun-Resistors_RESISTOR0805-RES"))
    )
    (comp (ref "R18")
      (value "40.2k")
      (footprint "eagle-import:0805")
      (libsource (lib "eagle-import") (part "SparkFun-Resistors_RESISTOR0805-RES"))
    )
    (comp (ref "R19")
      (value "47.5")
      (footprint "eagle-import:0805")
      (libsource (lib "eagle-import") (part "SparkFun-Resistors_RESISTOR0805-RES"))
    )
    (comp (ref "R20")
      (value "470k")
      (footprint "eagle-import:0805")
      (libsource (lib "eagle-import") (part "SparkFun-Resistors_RESISTOR0805-RES"))
    )
    (comp (ref "R21")
      (value "47.5")
      (footprint "eagle-import:0805")
      (libsource (lib "eagle-import") (part "SparkFun-Resistors_RESISTOR0805-RES"))
    )
    (comp (ref "R22")
      (value "470k")
      (footprint "eagle-import:0805")
      (libsource (lib "eagle-import") (part "SparkFun-Resistors_RESISTOR0805-RES"))
    )
    (comp (ref "R23")
      (value "47.5")
      (footprint "eagle-import:0805")
      (libsource (lib "eagle-import") (part "SparkFun-Resistors_RESISTOR0805-RES"))
    )
    (comp (ref "R24")
      (value "470k")
      (footprint "eagle-import:0805")
      (libsource (lib "eagle-import") (part "SparkFun-Resistors_RESISTOR0805-RES"))
    )
    (comp (ref "R25")
      (value "47.5")
      (footprint "eagle-import:0805")
      (libsource (lib "eagle-import") (part "SparkFun-Resistors_RESISTOR0805-RES"))
    )
    (comp (ref "R26")
      (value "47.5")
      (footprint "eagle-import:0805")
      (libsource (lib "eagle-import") (part "SparkFun-Resistors_RESISTOR0805-RES"))
    )
    (comp (ref "R27")
      (value "47.5")
      (footprint "eagle-import:0805")
      (libsource (lib "eagle-import") (part "SparkFun-Resistors_RESISTOR0805-RES"))
    )
    (comp (ref "R28")
      (value "470k")
      (footprint "eagle-import:0805")
      (libsource (lib "eagle-import") (part "SparkFun-Resistors_RESISTOR0805-RES"))
    )
    (comp (ref "R29")
      (value "470k")
      (footprint "eagle-import:0805")
      (libsource (lib "eagle-import") (part "SparkFun-Resistors_RESISTOR0805-RES"))
    )
    (comp (ref "R30")
      (value "470k")
      (footprint "eagle-import:0805")
      (libsource (lib "eagle-import") (part "SparkFun-Resistors_RESISTOR0805-RES"))
    )
    (comp (ref "R31")
      (value "40.2k")
      (footprint "eagle-import:0805")
      (libsource (lib "eagle-import") (part "SparkFun-Resistors_RESISTOR0805-RES"))
    )
    (comp (ref "R32")
      (value "47.5")
      (footprint "eagle-import:0805")
      (libsource (lib "eagle-import") (part "SparkFun-Resistors_RESISTOR0805-RES"))
    )
    (comp (ref "R33")
      (value "470k")
      (footprint "eagle-import:0805")
      (libsource (lib "eagle-import") (part "SparkFun-Resistors_RESISTOR0805-RES"))
    )
    (comp (ref "R34")
      (value "47.5")
      (footprint "eagle-import:0805")
      (libsource (lib "eagle-import") (part "SparkFun-Resistors_RESISTOR0805-RES"))
    )
    (comp (ref "R35")
      (value "470k")
      (footprint "eagle-import:0805")
      (libsource (lib "eagle-import") (part "SparkFun-Resistors_RESISTOR0805-RES"))
    )
    (comp (ref "R36")
      (value "47.5")
      (footprint "eagle-import:0805")
      (libsource (lib "eagle-import") (part "SparkFun-Resistors_RESISTOR0805-RES"))
    )
    (comp (ref "R37")
      (value "470k")
      (footprint "eagle-import:0805")
      (libsource (lib "eagle-import") (part "SparkFun-Resistors_RESISTOR0805-RES"))
    )
    (comp (ref "R38")
      (value "47.5")
      (footprint "eagle-import:0805")
      (libsource (lib "eagle-import") (part "SparkFun-Resistors_RESISTOR0805-RES"))
    )
    (comp (ref "R39")
      (value "47.5")
      (footprint "eagle-import:0805")
      (libsource (lib "eagle-import") (part "SparkFun-Resistors_RESISTOR0805-RES"))
    )
    (comp (ref "R40")
      (value "47.5")
      (footprint "eagle-import:0805")
      (libsource (lib "eagle-import") (part "SparkFun-Resistors_RESISTOR0805-RES"))
    )
    (comp (ref "R41")
      (value "470k")
      (footprint "eagle-import:0805")
      (libsource (lib "eagle-import") (part "SparkFun-Resistors_RESISTOR0805-RES"))
    )
    (comp (ref "R42")
      (value "470k")
      (footprint "eagle-import:0805")
      (libsource (lib "eagle-import") (part "SparkFun-Resistors_RESISTOR0805-RES"))
    )
    (comp (ref "R43")
      (value "470k")
      (footprint "eagle-import:0805")
      (libsource (lib "eagle-import") (part "SparkFun-Resistors_RESISTOR0805-RES"))
    )
    (comp (ref "R44")
      (value "40.2k")
      (footprint "eagle-import:0805")
      (libsource (lib "eagle-import") (part "SparkFun-Resistors_RESISTOR0805-RES"))
    )
    (comp (ref "R45")
      (value "47.5")
      (footprint "eagle-import:0805")
      (libsource (lib "eagle-import") (part "SparkFun-Resistors_RESISTOR0805-RES"))
    )
    (comp (ref "R46")
      (value "470k")
      (footprint "eagle-import:0805")
      (libsource (lib "eagle-import") (part "SparkFun-Resistors_RESISTOR0805-RES"))
    )
    (comp (ref "R47")
      (value "47.5")
      (footprint "eagle-import:0805")
      (libsource (lib "eagle-import") (part "SparkFun-Resistors_RESISTOR0805-RES"))
    )
    (comp (ref "R48")
      (value "470k")
      (footprint "eagle-import:0805")
      (libsource (lib "eagle-import") (part "SparkFun-Resistors_RESISTOR0805-RES"))
    )
    (comp (ref "R49")
      (value "47.5")
      (footprint "eagle-import:0805")
      (libsource (lib "eagle-import") (part "SparkFun-Resistors_RESISTOR0805-RES"))
    )
    (comp (ref "R50")
      (value "470k")
      (footprint "eagle-import:0805")
      (libsource (lib "eagle-import") (part "SparkFun-Resistors_RESISTOR0805-RES"))
    )
    (comp (ref "R51")
      (value "47.5")
      (footprint "eagle-import:0805")
      (libsource (lib "eagle-import") (part "SparkFun-Resistors_RESISTOR0805-RES"))
    )
    (comp (ref "R52")
      (value "47.5")
      (footprint "eagle-import:0805")
      (libsource (lib "eagle-import") (part "SparkFun-Resistors_RESISTOR0805-RES"))
    )
    (comp (ref "R53")
      (value "47.5")
      (footprint "eagle-import:0805")
      (libsource (lib "eagle-import") (part "SparkFun-Resistors_RESISTOR0805-RES"))
    )
    (comp (ref "R54")
      (value "470k")
      (footprint "eagle-import:0805")
      (libsource (lib "eagle-import") (part "SparkFun-Resistors_RESISTOR0805-RES"))
    )
    (comp (ref "R55")
      (value "470k")
      (footprint "eagle-import:0805")
      (libsource (lib "eagle-import") (part "SparkFun-Resistors_RESISTOR0805-RES"))
    )
    (comp (ref "R56")
      (value "470k")
      (footprint "eagle-import:0805")
      (libsource (lib "eagle-import") (part "SparkFun-Resistors_RESISTOR0805-RES"))
    )
    (comp (ref "R57")
      (value "3k")
      (footprint "eagle-import:0805")
      (libsource (lib "eagle-import") (part "SparkFun-Resistors_RESISTOR0805-RES"))
    )
    (comp (ref "R58")
      (value "3k")
      (footprint "eagle-import:0805")
      (libsource (lib "eagle-import") (part "SparkFun-Resistors_RESISTOR0805-RES"))
    )
    (comp (ref "R59")
      (value "3k")
      (footprint "eagle-import:0805")
      (libsource (lib "eagle-import") (part "SparkFun-Resistors_RESISTOR0805-RES"))
    )
    (comp (ref "R60")
      (value "2k")
      (footprint "eagle-import:0805")
      (libsource (lib "eagle-import") (part "RESISTOR0805-RES"))
    )
    (comp (ref "R61")
      (value "2k")
      (footprint "eagle-import:0805")
      (libsource (lib "eagle-import") (part "RESISTOR0805-RES"))
    )
    (comp (ref "R62")
      (value "66.5k")
      (footprint "eagle-import:0805")
      (libsource (lib "eagle-import") (part "SparkFun-Resistors_RESISTOR0805-RES"))
    )
    (comp (ref "R63")
      (value "1k")
      (footprint "eagle-import:0805")
      (libsource (lib "eagle-import") (part "SparkFun-Resistors_RESISTOR0805-RES"))
    )
    (comp (ref "R64")
      (value "1k")
      (footprint "eagle-import:0805")
      (libsource (lib "eagle-import") (part "SparkFun-Resistors_RESISTOR0805-RES"))
    )
    (comp (ref "R65")
      (value "10k")
      (footprint "eagle-import:0805")
      (libsource (lib "eagle-import") (part "SparkFun-Resistors_RESISTOR0805-RES"))
    )
    (comp (ref "R66")
      (value "10k")
      (footprint "eagle-import:0805")
      (libsource (lib "eagle-import") (part "SparkFun-Resistors_RESISTOR0805-RES"))
    )
    (comp (ref "R67")
      (value "10k")
      (footprint "eagle-import:0805")
      (libsource (lib "eagle-import") (part "SparkFun-Resistors_RESISTOR0805-RES"))
    )
    (comp (ref "R68")
      (value "10k")
      (footprint "eagle-import:0805")
      (libsource (lib "eagle-import") (part "SparkFun-Resistors_RESISTOR0805-RES"))
    )
    (comp (ref "R69")
      (value "10k")
      (footprint "eagle-import:0805")
      (libsource (lib "eagle-import") (part "SparkFun-Resistors_RESISTOR0805-RES"))
    )
    (comp (ref "R70")
      (value "10k")
      (footprint "eagle-import:0805")
      (libsource (lib "eagle-import") (part "SparkFun-Resistors_RESISTOR0805-RES"))
    )
    (comp (ref "R71")
      (value "10k")
      (footprint "eagle-import:0805")
      (libsource (lib "eagle-import") (part "SparkFun-Resistors_RESISTOR0805-RES"))
    )
    (comp (ref "R72")
      (value "10k")
      (footprint "eagle-import:0805")
      (libsource (lib "eagle-import") (part "SparkFun-Resistors_RESISTOR0805-RES"))
    )
    (comp (ref "R73")
      (value "10k")
      (footprint "eagle-import:0805")
      (libsource (lib "eagle-import") (part "SparkFun-Resistors_RESISTOR0805-RES"))
    )
    (comp (ref "R74")
      (value "2k")
      (footprint "eagle-import:0805")
      (libsource (lib "eagle-import") (part "RESISTOR0805-RES"))
    )
    (comp (ref "R75")
      (value "2k")
      (footprint "eagle-import:0805")
      (libsource (lib "eagle-import") (part "RESISTOR0805-RES"))
    )
    (comp (ref "R76")
      (value "30k")
      (footprint "eagle-import:0805")
      (libsource (lib "eagle-import") (part "RESISTOR0805-RES"))
    )
    (comp (ref "R77")
      (value "3k")
      (footprint "eagle-import:0805")
      (libsource (lib "eagle-import") (part "SparkFun-Resistors_RESISTOR0805-RES"))
    )
    (comp (ref "R78")
      (value "1k")
      (footprint "eagle-import:0805")
      (libsource (lib "eagle-import") (part "SparkFun-Resistors_RESISTOR0805-RES"))
    )
    (comp (ref "R79")
      (value "1k")
      (footprint "eagle-import:0805")
      (libsource (lib "eagle-import") (part "SparkFun-Resistors_RESISTOR0805-RES"))
    )
    (comp (ref "R80")
      (value "37.5k")
      (footprint "eagle-import:0805")
      (libsource (lib "eagle-import") (part "SparkFun-Resistors_RESISTOR0805-RES"))
    )
    (comp (ref "R81")
      (value "1k")
      (footprint "eagle-import:0805")
      (libsource (lib "eagle-import") (part "SparkFun-Resistors_RESISTOR0805-RES"))
    )
    (comp (ref "R82")
      (value "1k")
      (footprint "eagle-import:0805")
      (libsource (lib "eagle-import") (part "SparkFun-Resistors_RESISTOR0805-RES"))
    )
    (comp (ref "R83")
      (value "30k")
      (footprint "eagle-import:0805")
      (libsource (lib "eagle-import") (part "RESISTOR0805-RES"))
    )
    (comp (ref "R84")
      (value "1k")
      (footprint "eagle-import:0805")
      (libsource (lib "eagle-import") (part "SparkFun-Resistors_RESISTOR0805-RES"))
    )
    (comp (ref "R85")
      (value "1k")
      (footprint "eagle-import:0805")
      (libsource (lib "eagle-import") (part "SparkFun-Resistors_RESISTOR0805-RES"))
    )
    (comp (ref "R86")
      (value "30k")
      (footprint "eagle-import:0805")
      (libsource (lib "eagle-import") (part "RESISTOR0805-RES"))
    )
    (comp (ref "R87")
      (value "1k")
      (footprint "eagle-import:0805")
      (libsource (lib "eagle-import") (part "SparkFun-Resistors_RESISTOR0805-RES"))
    )
    (comp (ref "R88")
      (value "1k")
      (footprint "eagle-import:0805")
      (libsource (lib "eagle-import") (part "SparkFun-Resistors_RESISTOR0805-RES"))
    )
    (comp (ref "R89")
      (value "30k")
      (footprint "eagle-import:0805")
      (libsource (lib "eagle-import") (part "RESISTOR0805-RES"))
    )
    (comp (ref "R90")
      (value "2k")
      (footprint "eagle-import:0805")
      (libsource (lib "eagle-import") (part "RESISTOR0805-RES"))
    )
    (comp (ref "R91")
      (value "1k")
      (footprint "eagle-import:0805")
      (libsource (lib "eagle-import") (part "SparkFun-Resistors_RESISTOR0805-RES"))
    )
    (comp (ref "R92")
      (value "1k")
      (footprint "eagle-import:0805")
      (libsource (lib "eagle-import") (part "SparkFun-Resistors_RESISTOR0805-RES"))
    )
    (comp (ref "R93")
      (value "66.5k")
      (footprint "eagle-import:0805")
      (libsource (lib "eagle-import") (part "SparkFun-Resistors_RESISTOR0805-RES"))
    )
    (comp (ref "R94")
      (value "37.5k")
      (footprint "eagle-import:0805")
      (libsource (lib "eagle-import") (part "SparkFun-Resistors_RESISTOR0805-RES"))
    )
    (comp (ref "R95")
      (value "66.5k")
      (footprint "eagle-import:0805")
      (libsource (lib "eagle-import") (part "SparkFun-Resistors_RESISTOR0805-RES"))
    )
    (comp (ref "R96")
      (value "37.5k")
      (footprint "eagle-import:0805")
      (libsource (lib "eagle-import") (part "SparkFun-Resistors_RESISTOR0805-RES"))
    )
    (comp (ref "R97")
      (value "10k")
      (footprint "eagle-import:0805")
      (libsource (lib "eagle-import") (part "RESISTOR0805-RES"))
    )
    (comp (ref "R98")
      (value "2k")
      (footprint "eagle-import:0805")
      (libsource (lib "eagle-import") (part "RESISTOR0805-RES"))
    )
    (comp (ref "R99")
      (value "1k")
      (footprint "eagle-import:0805")
      (libsource (lib "eagle-import") (part "RESISTOR0805-RES"))
    )
    (comp (ref "R100")
      (value "30k")
      (footprint "eagle-import:0805")
      (libsource (lib "eagle-import") (part "RESISTOR0805-RES"))
    )
    (comp (ref "R101")
      (value "1k")
      (footprint "eagle-import:0805")
      (libsource (lib "eagle-import") (part "RESISTOR0805-RES"))
    )
    (comp (ref "R102")
      (value "66.5k")
      (footprint "eagle-import:0805")
      (libsource (lib "eagle-import") (part "SparkFun-Resistors_RESISTOR0805-RES"))
    )
    (comp (ref "R103")
      (value "1k")
      (footprint "eagle-import:0805")
      (libsource (lib "eagle-import") (part "RESISTOR0805-RES"))
    )
    (comp (ref "R104")
      (value "37.5k")
      (footprint "eagle-import:0805")
      (libsource (lib "eagle-import") (part "SparkFun-Resistors_RESISTOR0805-RES"))
    )
    (comp (ref "R105")
      (value "10k")
      (footprint "eagle-import:0805")
      (libsource (lib "eagle-import") (part "SparkFun-Resistors_RESISTOR0805-RES"))
    )
    (comp (ref "R106")
      (value "10k")
      (footprint "eagle-import:0805")
      (libsource (lib "eagle-import") (part "SparkFun-Resistors_RESISTOR0805-RES"))
    )
    (comp (ref "R107")
      (value "10k")
      (footprint "eagle-import:0805")
      (libsource (lib "eagle-import") (part "SparkFun-Resistors_RESISTOR0805-RES"))
    )
    (comp (ref "R108")
      (value "30k")
      (footprint "eagle-import:0805")
      (libsource (lib "eagle-import") (part "RESISTOR0805-RES"))
    )
    (comp (ref "R109")
      (value "2k")
      (footprint "eagle-import:0805")
      (libsource (lib "eagle-import") (part "RESISTOR0805-RES"))
    )
    (comp (ref "R110")
      (value "2k")
      (footprint "eagle-import:0805")
      (libsource (lib "eagle-import") (part "RESISTOR0805-RES"))
    )
    (comp (ref "R111")
      (value "30k")
      (footprint "eagle-import:0805")
      (libsource (lib "eagle-import") (part "RESISTOR0805-RES"))
    )
    (comp (ref "R112")
      (value "30k")
      (footprint "eagle-import:0805")
      (libsource (lib "eagle-import") (part "RESISTOR0805-RES"))
    )
    (comp (ref "R113")
      (value "10k")
      (footprint "eagle-import:0805")
      (libsource (lib "eagle-import") (part "RESISTOR0805-RES"))
    )
    (comp (ref "R114")
      (value "1M")
      (footprint "eagle-import:0805")
      (libsource (lib "eagle-import") (part "SparkFun-Resistors_RESISTOR0805-RES"))
    )
    (comp (ref "R115")
      (value "1M")
      (footprint "eagle-import:0805")
      (libsource (lib "eagle-import") (part "SparkFun-Resistors_RESISTOR0805-RES"))
    )
    (comp (ref "R116")
      (value "1M")
      (footprint "eagle-import:0805")
      (libsource (lib "eagle-import") (part "SparkFun-Resistors_RESISTOR0805-RES"))
    )
    (comp (ref "R117")
      (value "1M")
      (footprint "eagle-import:0805")
      (libsource (lib "eagle-import") (part "SparkFun-Resistors_RESISTOR0805-RES"))
    )
    (comp (ref "RSENSE1")
      (value ".02")
      (footprint "eagle-import:R2512")
      (libsource (lib "eagle-import") (part "SparkFun-Resistors_RESISTOR2512"))
    )
    (comp (ref "RSENSE2")
      (value ".02")
      (footprint "eagle-import:R2512")
      (libsource (lib "eagle-import") (part "SparkFun-Resistors_RESISTOR2512"))
    )
    (comp (ref "RSENSE3")
      (value ".02")
      (footprint "eagle-import:R2512")
      (libsource (lib "eagle-import") (part "SparkFun-Resistors_RESISTOR2512"))
    )
    (comp (ref "RSENSE4")
      (value ".02")
      (footprint "eagle-import:R2512")
      (libsource (lib "eagle-import") (part "SparkFun-Resistors_RESISTOR2512"))
    )
    (comp (ref "S1")
      (value "SWITCH-MOMENTARY-2SMD-4")
      (footprint "eagle-import:TACTILE_SWITCH_TALL")
      (libsource (lib "eagle-import") (part "SWITCH-MOMENTARY-2SMD-4"))
    )
    (comp (ref "SENSE1")
      (value "TEST_PT")
      (footprint "eagle-import:TESTING_PT")
      (libsource (lib "eagle-import") (part "TEST_PT"))
    )
    (comp (ref "SENSE2")
      (value "TEST_PT")
      (footprint "eagle-import:TESTING_PT")
      (libsource (lib "eagle-import") (part "TEST_PT"))
    )
    (comp (ref "SENSE3")
      (value "TEST_PT")
      (footprint "eagle-import:TESTING_PT")
      (libsource (lib "eagle-import") (part "TEST_PT"))
    )
    (comp (ref "SENSE4")
      (value "TEST_PT")
      (footprint "eagle-import:TESTING_PT")
      (libsource (lib "eagle-import") (part "TEST_PT"))
    )
    (comp (ref "SPARE_HEADER")
      (value "M10LOCK")
      (footprint "eagle-import:1X10_LOCK")
      (libsource (lib "eagle-import") (part "M10LOCK"))
    )
    (comp (ref "SPI_HEADER")
      (value "M10LOCK")
      (footprint "eagle-import:1X10_LOCK")
      (libsource (lib "eagle-import") (part "M10LOCK"))
    )
    (comp (ref "U$1")
      (value "A4915")
      (footprint "eagle-import:TSSOP28-GROUNDPAD")
      (libsource (lib "eagle-import") (part "A4915"))
    )
    (comp (ref "U$2")
      (value "A4915")
      (footprint "eagle-import:TSSOP28-GROUNDPAD")
      (libsource (lib "eagle-import") (part "A4915"))
    )
    (comp (ref "U$3")
      (value "A4915")
      (footprint "eagle-import:TSSOP28-GROUNDPAD")
      (libsource (lib "eagle-import") (part "A4915"))
    )
    (comp (ref "U$4")
      (value "A4915")
      (footprint "eagle-import:TSSOP28-GROUNDPAD")
      (libsource (lib "eagle-import") (part "A4915"))
    )
    (comp (ref "U$5")
      (value "MCP9700SMD")
      (footprint "eagle-import:SOT23-3")
      (libsource (lib "eagle-import") (part "MCP9700SMD"))
    )
    (comp (ref "U$6")
      (value "MCP9700SMD")
      (footprint "eagle-import:SOT23-3")
      (libsource (lib "eagle-import") (part "MCP9700SMD"))
    )
    (comp (ref "U$7")
      (value "MCP9700SMD")
      (footprint "eagle-import:SOT23-3")
      (libsource (lib "eagle-import") (part "MCP9700SMD"))
    )
    (comp (ref "U$8")
      (value "MCP9700SMD")
      (footprint "eagle-import:SOT23-3")
      (libsource (lib "eagle-import") (part "MCP9700SMD"))
    )
    (comp (ref "U2")
      (value "ATMEGA165PV-8AU")
      (footprint "eagle-import:QFP80P1600X1600X120-64N")
      (libsource (lib "eagle-import") (part "ATMEGA165PV-8AU"))
    )
  )
  (nets
    (net (code "1") (name "/3.3V") (class "Default")
      (node (ref "C15") (pin "2") (pinfunction "2_2") (pintype "passive"))
      (node (ref "C24") (pin "2") (pinfunction "2_2") (pintype "passive"))
      (node (ref "C39") (pin "2") (pinfunction "2_2") (pintype "passive"))
      (node (ref "C45") (pin "1") (pinfunction "1_1") (pintype "passive"))
      (node (ref "C46") (pin "1") (pinfunction "1_1") (pintype "passive"))
      (node (ref "C6") (pin "2") (pinfunction "2_2") (pintype "passive"))
      (node (ref "C60") (pin "1") (pinfunction "1_1") (pintype "passive"))
      (node (ref "C62") (pin "1") (pinfunction "1_1") (pintype "passive"))
      (node (ref "C63") (pin "1") (pinfunction "1_1") (pintype "passive"))
      (node (ref "C69") (pin "1") (pinfunction "1_1") (pintype "passive"))
      (node (ref "C71") (pin "1") (pinfunction "1_1") (pintype "passive"))
      (node (ref "JP1") (pin "2") (pinfunction "2_2") (pintype "passive"))
      (node (ref "LOGIC_HEADER") (pin "5") (pinfunction "5_5") (pintype "passive"))
      (node (ref "LOGIC_HEADER") (pin "6") (pinfunction "6_6") (pintype "passive"))
      (node (ref "LOGIC_HEADER") (pin "7") (pinfunction "7_7") (pintype "passive"))
      (node (ref "R113") (pin "2") (pinfunction "2_2") (pintype "passive"))
      (node (ref "R63") (pin "2") (pinfunction "2_2") (pintype "passive"))
      (node (ref "R64") (pin "2") (pinfunction "2_2") (pintype "passive"))
      (node (ref "R91") (pin "2") (pinfunction "2_2") (pintype "passive"))
      (node (ref "R92") (pin "2") (pinfunction "2_2") (pintype "passive"))
      (node (ref "R97") (pin "2") (pinfunction "2_2") (pintype "passive"))
      (node (ref "U$1") (pin "SPEED") (pinfunction "SPEED_SPEED") (pintype "bidirectional"))
      (node (ref "U$1") (pin "VDD") (pinfunction "VDD_VDD") (pintype "bidirectional"))
      (node (ref "U$2") (pin "SPEED") (pinfunction "SPEED_SPEED") (pintype "bidirectional"))
      (node (ref "U$2") (pin "VDD") (pinfunction "VDD_VDD") (pintype "bidirectional"))
      (node (ref "U$3") (pin "SPEED") (pinfunction "SPEED_SPEED") (pintype "bidirectional"))
      (node (ref "U$3") (pin "VDD") (pinfunction "VDD_VDD") (pintype "bidirectional"))
      (node (ref "U$4") (pin "SPEED") (pinfunction "SPEED_SPEED") (pintype "bidirectional"))
      (node (ref "U$4") (pin "VDD") (pinfunction "VDD_VDD") (pintype "bidirectional"))
      (node (ref "U$5") (pin "1") (pinfunction "VCC_1") (pintype "bidirectional"))
      (node (ref "U$6") (pin "1") (pinfunction "VCC_1") (pintype "bidirectional"))
      (node (ref "U$7") (pin "1") (pinfunction "VCC_1") (pintype "bidirectional"))
      (node (ref "U$8") (pin "1") (pinfunction "VCC_1") (pintype "bidirectional"))
      (node (ref "U2") (pin "21") (pinfunction "VCC_2_21") (pintype "power_in"))
      (node (ref "U2") (pin "52") (pinfunction "VCC_52") (pintype "power_in"))
    )
    (net (code "2") (name "/5V") (class "Default")
      (node (ref "C51") (pin "2") (pinfunction "2_2") (pintype "passive"))
      (node (ref "C52") (pin "2") (pinfunction "2_2") (pintype "passive"))
      (node (ref "C53") (pin "2") (pinfunction "2_2") (pintype "passive"))
      (node (ref "C54") (pin "2") (pinfunction "2_2") (pintype "passive"))
      (node (ref "C55") (pin "2") (pinfunction "2_2") (pintype "passive"))
      (node (ref "C56") (pin "2") (pinfunction "2_2") (pintype "passive"))
      (node (ref "C57") (pin "2") (pinfunction "2_2") (pintype "passive"))
      (node (ref "C58") (pin "2") (pinfunction "2_2") (pintype "passive"))
      (node (ref "C59") (pin "1") (pinfunction "1_1") (pintype "passive"))
      (node (ref "C61") (pin "1") (pinfunction "1_1") (pintype "passive"))
      (node (ref "C64") (pin "1") (pinfunction "1_1") (pintype "passive"))
      (node (ref "C70") (pin "2") (pinfunction "2_2") (pintype "passive"))
      (node (ref "C72") (pin "2") (pinfunction "2_2") (pintype "passive"))
      (node (ref "COMP1") (pin "5") (pinfunction "V+_5") (pintype "power_in"))
      (node (ref "COMP2") (pin "5") (pinfunction "V+_5") (pintype "power_in"))
      (node (ref "COMP3") (pin "5") (pinfunction "V+_5") (pintype "power_in"))
      (node (ref "COMP4") (pin "5") (pinfunction "V+_5") (pintype "power_in"))
      (node (ref "LOGIC_HEADER") (pin "10") (pinfunction "10_10") (pintype "passive"))
      (node (ref "LOGIC_HEADER") (pin "8") (pinfunction "8_8") (pintype "passive"))
      (node (ref "LOGIC_HEADER") (pin "9") (pinfunction "9_9") (pintype "passive"))
      (node (ref "MOTOR1") (pin "1") (pinfunction "P$11_1") (pintype "bidirectional"))
      (node (ref "MOTOR2") (pin "1") (pinfunction "P$11_1") (pintype "bidirectional"))
      (node (ref "MOTOR3") (pin "1") (pinfunction "P$11_1") (pintype "bidirectional"))
      (node (ref "MOTOR4") (pin "1") (pinfunction "P$11_1") (pintype "bidirectional"))
      (node (ref "OP1") (pin "5") (pinfunction "V+_5") (pintype "power_in"))
      (node (ref "OP2") (pin "5") (pinfunction "V+_5") (pintype "power_in"))
      (node (ref "OP3") (pin "5") (pinfunction "V+_5") (pintype "power_in"))
      (node (ref "OP4") (pin "5") (pinfunction "V+_5") (pintype "power_in"))
      (node (ref "QUAD1") (pin "1") (pinfunction "1_1") (pintype "passive"))
      (node (ref "QUAD2") (pin "1") (pinfunction "1_1") (pintype "passive"))
      (node (ref "QUAD3") (pin "1") (pinfunction "1_1") (pintype "passive"))
      (node (ref "QUAD4") (pin "1") (pinfunction "1_1") (pintype "passive"))
      (node (ref "R102") (pin "2") (pinfunction "2_2") (pintype "passive"))
      (node (ref "R105") (pin "2") (pinfunction "2_2") (pintype "passive"))
      (node (ref "R106") (pin "2") (pinfunction "2_2") (pintype "passive"))
      (node (ref "R107") (pin "2") (pinfunction "2_2") (pintype "passive"))
      (node (ref "R62") (pin "2") (pinfunction "2_2") (pintype "passive"))
      (node (ref "R65") (pin "2") (pinfunction "2_2") (pintype "passive"))
      (node (ref "R66") (pin "2") (pinfunction "2_2") (pintype "passive"))
      (node (ref "R67") (pin "2") (pinfunction "2_2") (pintype "passive"))
      (node (ref "R68") (pin "2") (pinfunction "2_2") (pintype "passive"))
      (node (ref "R69") (pin "2") (pinfunction "2_2") (pintype "passive"))
      (node (ref "R70") (pin "2") (pinfunction "2_2") (pintype "passive"))
      (node (ref "R71") (pin "2") (pinfunction "2_2") (pintype "passive"))
      (node (ref "R72") (pin "2") (pinfunction "2_2") (pintype "passive"))
      (node (ref "R73") (pin "2") (pinfunction "2_2") (pintype "passive"))
      (node (ref "R93") (pin "2") (pinfunction "2_2") (pintype "passive"))
      (node (ref "R95") (pin "2") (pinfunction "2_2") (pintype "passive"))
    )
    (net (code "3") (name "/12V") (class "Default")
      (node (ref "C13") (pin "1") (pinfunction "1_1") (pintype "passive"))
      (node (ref "C16") (pin "+") (pinfunction "+_+") (pintype "passive"))
      (node (ref "C17") (pin "1") (pinfunction "1_1") (pintype "passive"))
      (node (ref "C2") (pin "+") (pinfunction "+_+") (pintype "passive"))
      (node (ref "C22") (pin "1") (pinfunction "1_1") (pintype "passive"))
      (node (ref "C25") (pin "+") (pinfunction "+_+") (pintype "passive"))
      (node (ref "C26") (pin "1") (pinfunction "1_1") (pintype "passive"))
      (node (ref "C31") (pin "1") (pinfunction "1_1") (pintype "passive"))
      (node (ref "C34") (pin "+") (pinfunction "+_+") (pintype "passive"))
      (node (ref "C35") (pin "1") (pinfunction "1_1") (pintype "passive"))
      (node (ref "C4") (pin "1") (pinfunction "1_1") (pintype "passive"))
      (node (ref "C41") (pin "+") (pinfunction "+_+") (pintype "passive"))
      (node (ref "C42") (pin "+") (pinfunction "+_+") (pintype "passive"))
      (node (ref "C43") (pin "+") (pinfunction "+_+") (pintype "passive"))
      (node (ref "C44") (pin "1") (pinfunction "1_1") (pintype "passive"))
      (node (ref "C50") (pin "+") (pinfunction "+_+") (pintype "passive"))
      (node (ref "C7") (pin "+") (pinfunction "+_+") (pintype "passive"))
      (node (ref "C8") (pin "1") (pinfunction "1_1") (pintype "passive"))
      (node (ref "D1") (pin "C") (pinfunction "C_C") (pintype "passive"))
      (node (ref "D2") (pin "C") (pinfunction "C_C") (pintype "passive"))
      (node (ref "D3") (pin "C") (pinfunction "C_C") (pintype "passive"))
      (node (ref "D5") (pin "C") (pinfunction "C_C") (pintype "passive"))
      (node (ref "POWER_HEADER") (pin "10") (pinfunction "10_10") (pintype "passive"))
      (node (ref "POWER_HEADER") (pin "6") (pinfunction "6_6") (pintype "passive"))
      (node (ref "POWER_HEADER") (pin "7") (pinfunction "7_7") (pintype "passive"))
      (node (ref "POWER_HEADER") (pin "8") (pinfunction "8_8") (pintype "passive"))
      (node (ref "POWER_HEADER") (pin "9") (pinfunction "9_9") (pintype "passive"))
      (node (ref "Q1") (pin "DRAIN") (pinfunction "P$1_DRAIN") (pintype "bidirectional"))
      (node (ref "Q10") (pin "DRAIN") (pinfunction "P$1_DRAIN") (pintype "bidirectional"))
      (node (ref "Q11") (pin "DRAIN") (pinfunction "P$1_DRAIN") (pintype "bidirectional"))
      (node (ref "Q17") (pin "DRAIN") (pinfunction "P$1_DRAIN") (pintype "bidirectional"))
      (node (ref "Q18") (pin "DRAIN") (pinfunction "P$1_DRAIN") (pintype "bidirectional"))
      (node (ref "Q19") (pin "DRAIN") (pinfunction "P$1_DRAIN") (pintype "bidirectional"))
      (node (ref "Q2") (pin "DRAIN") (pinfunction "P$1_DRAIN") (pintype "bidirectional"))
      (node (ref "Q25") (pin "DRAIN") (pinfunction "P$1_DRAIN") (pintype "bidirectional"))
      (node (ref "Q26") (pin "DRAIN") (pinfunction "P$1_DRAIN") (pintype "bidirectional"))
      (node (ref "Q27") (pin "DRAIN") (pinfunction "P$1_DRAIN") (pintype "bidirectional"))
      (node (ref "Q6") (pin "DRAIN") (pinfunction "P$1_DRAIN") (pintype "bidirectional"))
      (node (ref "Q9") (pin "DRAIN") (pinfunction "P$1_DRAIN") (pintype "bidirectional"))
      (node (ref "U$1") (pin "VBB") (pinfunction "VBB_VBB") (pintype "bidirectional"))
      (node (ref "U$2") (pin "VBB") (pinfunction "VBB_VBB") (pintype "bidirectional"))
      (node (ref "U$3") (pin "VBB") (pinfunction "VBB_VBB") (pintype "bidirectional"))
      (node (ref "U$4") (pin "VBB") (pinfunction "VBB_VBB") (pintype "bidirectional"))
    )
    (net (code "4") (name "/12VGND") (class "Default")
      (node (ref "C16") (pin "-") (pinfunction "-_-") (pintype "passive"))
      (node (ref "C17") (pin "2") (pinfunction "2_2") (pintype "passive"))
      (node (ref "C2") (pin "-") (pinfunction "-_-") (pintype "passive"))
      (node (ref "C25") (pin "-") (pinfunction "-_-") (pintype "passive"))
      (node (ref "C26") (pin "2") (pinfunction "2_2") (pintype "passive"))
      (node (ref "C34") (pin "-") (pinfunction "-_-") (pintype "passive"))
      (node (ref "C35") (pin "2") (pinfunction "2_2") (pintype "passive"))
      (node (ref "C41") (pin "-") (pinfunction "-_-") (pintype "passive"))
      (node (ref "C42") (pin "-") (pinfunction "-_-") (pintype "passive"))
      (node (ref "C43") (pin "-") (pinfunction "-_-") (pintype "passive"))
      (node (ref "C44") (pin "2") (pinfunction "2_2") (pintype "passive"))
      (node (ref "C50") (pin "-") (pinfunction "-_-") (pintype "passive"))
      (node (ref "C7") (pin "-") (pinfunction "-_-") (pintype "passive"))
      (node (ref "C8") (pin "2") (pinfunction "2_2") (pintype "passive"))
      (node (ref "D1") (pin "A") (pinfunction "A_A") (pintype "passive"))
      (node (ref "D2") (pin "A") (pinfunction "A_A") (pintype "passive"))
      (node (ref "D3") (pin "A") (pinfunction "A_A") (pintype "passive"))
      (node (ref "D5") (pin "A") (pinfunction "A_A") (pintype "passive"))
      (node (ref "POWER_HEADER") (pin "1") (pinfunction "1_1") (pintype "passive"))
      (node (ref "POWER_HEADER") (pin "2") (pinfunction "2_2") (pintype "passive"))
      (node (ref "POWER_HEADER") (pin "3") (pinfunction "3_3") (pintype "passive"))
      (node (ref "POWER_HEADER") (pin "4") (pinfunction "4_4") (pintype "passive"))
      (node (ref "POWER_HEADER") (pin "5") (pinfunction "5_5") (pintype "passive"))
      (node (ref "R110") (pin "1") (pinfunction "1_1") (pintype "passive"))
      (node (ref "R61") (pin "1") (pinfunction "1_1") (pintype "passive"))
      (node (ref "R75") (pin "1") (pinfunction "1_1") (pintype "passive"))
      (node (ref "R98") (pin "1") (pinfunction "1_1") (pintype "passive"))
      (node (ref "RSENSE1") (pin "1") (pinfunction "1_1") (pintype "passive"))
      (node (ref "RSENSE2") (pin "1") (pinfunction "1_1") (pintype "passive"))
      (node (ref "RSENSE3") (pin "1") (pinfunction "1_1") (pintype "passive"))
      (node (ref "RSENSE4") (pin "1") (pinfunction "1_1") (pintype "passive"))
    )
    (net (code "5") (name "/BREN") (class "Default")
      (node (ref "R79") (pin "2") (pinfunction "2_2") (pintype "passive"))
      (node (ref "R82") (pin "2") (pinfunction "2_2") (pintype "passive"))
      (node (ref "R85") (pin "2") (pinfunction "2_2") (pintype "passive"))
      (node (ref "R88") (pin "2") (pinfunction "2_2") (pintype "passive"))
      (node (ref "U2") (pin "29") (pinfunction "PD4_29") (pintype "bidirectional"))
    )
    (net (code "6") (name "/DIR1") (class "Default")
      (node (ref "R78") (pin "2") (pinfunction "2_2") (pintype "passive"))
      (node (ref "U2") (pin "25") (pinfunction "PD0_25") (pintype "bidirectional"))
    )
    (net (code "7") (name "/DIR2") (class "Default")
      (node (ref "R81") (pin "2") (pinfunction "2_2") (pintype "passive"))
      (node (ref "U2") (pin "26") (pinfunction "PD1_26") (pintype "bidirectional"))
    )
    (net (code "8") (name "/DIR3") (class "Default")
      (node (ref "R87") (pin "2") (pinfunction "2_2") (pintype "passive"))
      (node (ref "U2") (pin "27") (pinfunction "PD2_27") (pintype "bidirectional"))
    )
    (net (code "9") (name "/DIR4") (class "Default")
      (node (ref "R84") (pin "2") (pinfunction "2_2") (pintype "passive"))
      (node (ref "U2") (pin "28") (pinfunction "PD3_28") (pintype "bidirectional"))
    )
    (net (code "10") (name "/FAULT1") (class "Default")
      (node (ref "R63") (pin "1") (pinfunction "1_1") (pintype "passive"))
      (node (ref "U$4") (pin "FAULT") (pinfunction "FAULT_FAULT") (pintype "bidirectional"))
      (node (ref "U2") (pin "33") (pinfunction "PG0_33") (pintype "bidirectional"))
    )
    (net (code "11") (name "/FAULT2") (class "Default")
      (node (ref "R64") (pin "1") (pinfunction "1_1") (pintype "passive"))
      (node (ref "U$1") (pin "FAULT") (pinfunction "FAULT_FAULT") (pintype "bidirectional"))
      (node (ref "U2") (pin "34") (pinfunction "PG1_34") (pintype "bidirectional"))
    )
    (net (code "12") (name "/FAULT3") (class "Default")
      (node (ref "R91") (pin "1") (pinfunction "1_1") (pintype "passive"))
      (node (ref "U$2") (pin "FAULT") (pinfunction "FAULT_FAULT") (pintype "bidirectional"))
      (node (ref "U2") (pin "43") (pinfunction "PG2_43") (pintype "bidirectional"))
    )
    (net (code "13") (name "/FAULT4") (class "Default")
      (node (ref "R92") (pin "1") (pinfunction "1_1") (pintype "passive"))
      (node (ref "U$3") (pin "FAULT") (pinfunction "FAULT_FAULT") (pintype "bidirectional"))
      (node (ref "U2") (pin "18") (pinfunction "PG3_18") (pintype "bidirectional"))
    )
    (net (code "14") (name "/GLED1") (class "Default")
      (node (ref "R1") (pin "2") (pinfunction "2_2") (pintype "passive"))
      (node (ref "U2") (pin "35") (pinfunction "PC0_35") (pintype "bidirectional"))
    )
    (net (code "15") (name "/GLED2") (class "Default")
      (node (ref "R99") (pin "2") (pinfunction "2_2") (pintype "passive"))
      (node (ref "U2") (pin "36") (pinfunction "PC1_36") (pintype "bidirectional"))
    )
    (net (code "16") (name "/GLED3") (class "Default")
      (node (ref "R101") (pin "2") (pinfunction "2_2") (pintype "passive"))
      (node (ref "U2") (pin "37") (pinfunction "PC2_37") (pintype "bidirectional"))
    )
    (net (code "17") (name "/GLED4") (class "Default")
      (node (ref "R103") (pin "2") (pinfunction "2_2") (pintype "passive"))
      (node (ref "U2") (pin "38") (pinfunction "PC3_38") (pintype "bidirectional"))
    )
    (net (code "18") (name "/LIM1") (class "Default")
      (node (ref "COMP1") (pin "4") (pinfunction "OUT_4") (pintype "output"))
      (node (ref "LIM1") (pin "P$1") (pinfunction "P$1_P$1") (pintype "bidirectional"))
      (node (ref "R114") (pin "1") (pinfunction "1_1") (pintype "passive"))
      (node (ref "R77") (pin "2") (pinfunction "2_2") (pintype "passive"))
      (node (ref "U$4") (pin "ENABLE") (pinfunction "ENABLE_ENABLE") (pintype "bidirectional"))
    )
    (net (code "19") (name "/LIM2") (class "Default")
      (node (ref "COMP2") (pin "4") (pinfunction "OUT_4") (pintype "output"))
      (node (ref "LIM2") (pin "P$1") (pinfunction "P$1_P$1") (pintype "bidirectional"))
      (node (ref "R115") (pin "1") (pinfunction "1_1") (pintype "passive"))
      (node (ref "R57") (pin "2") (pinfunction "2_2") (pintype "passive"))
      (node (ref "U$1") (pin "ENABLE") (pinfunction "ENABLE_ENABLE") (pintype "bidirectional"))
    )
    (net (code "20") (name "/LIM3") (class "Default")
      (node (ref "COMP3") (pin "4") (pinfunction "OUT_4") (pintype "output"))
      (node (ref "LIM3") (pin "P$1") (pinfunction "P$1_P$1") (pintype "bidirectional"))
      (node (ref "R116") (pin "1") (pinfunction "1_1") (pintype "passive"))
      (node (ref "R59") (pin "2") (pinfunction "2_2") (pintype "passive"))
      (node (ref "U$2") (pin "ENABLE") (pinfunction "ENABLE_ENABLE") (pintype "bidirectional"))
    )
    (net (code "21") (name "/LIM4") (class "Default")
      (node (ref "COMP4") (pin "4") (pinfunction "OUT_4") (pintype "output"))
      (node (ref "LIM4") (pin "P$1") (pinfunction "P$1_P$1") (pintype "bidirectional"))
      (node (ref "R117") (pin "1") (pinfunction "1_1") (pintype "passive"))
      (node (ref "R58") (pin "2") (pinfunction "2_2") (pintype "passive"))
      (node (ref "U$3") (pin "ENABLE") (pinfunction "ENABLE_ENABLE") (pintype "bidirectional"))
    )
    (net (code "22") (name "/M1H1") (class "Default")
      (node (ref "MOTOR1") (pin "3") (pinfunction "P$9_3") (pintype "bidirectional"))
      (node (ref "R106") (pin "1") (pinfunction "1_1") (pintype "passive"))
      (node (ref "U$4") (pin "HA") (pinfunction "HA_HA") (pintype "bidirectional"))
    )
    (net (code "23") (name "/M1H2") (class "Default")
      (node (ref "MOTOR1") (pin "4") (pinfunction "P$8_4") (pintype "bidirectional"))
      (node (ref "R107") (pin "1") (pinfunction "1_1") (pintype "passive"))
      (node (ref "U$4") (pin "HB") (pinfunction "HB_HB") (pintype "bidirectional"))
    )
    (net (code "24") (name "/M1H3") (class "Default")
      (node (ref "MOTOR1") (pin "2") (pinfunction "P$10_2") (pintype "bidirectional"))
      (node (ref "R105") (pin "1") (pinfunction "1_1") (pintype "passive"))
      (node (ref "U$4") (pin "HC") (pinfunction "HC_HC") (pintype "bidirectional"))
    )
    (net (code "25") (name "/M1O1") (class "Default")
      (node (ref "C9") (pin "2") (pinfunction "2_2") (pintype "passive"))
      (node (ref "M1O1") (pin "P$1") (pinfunction "P$1_P$1") (pintype "bidirectional"))
      (node (ref "MOTOR1") (pin "10") (pinfunction "P$2_10") (pintype "bidirectional"))
      (node (ref "MOTOR1") (pin "11") (pinfunction "P$1_11") (pintype "bidirectional"))
      (node (ref "Q3") (pin "DRAIN") (pinfunction "P$1_DRAIN") (pintype "bidirectional"))
      (node (ref "Q6") (pin "SOURCE") (pinfunction "P$2_SOURCE") (pintype "bidirectional"))
      (node (ref "R7") (pin "2") (pinfunction "2_2") (pintype "passive"))
      (node (ref "U$4") (pin "SA") (pinfunction "SA_SA") (pintype "bidirectional"))
    )
    (net (code "26") (name "/M1O2") (class "Default")
      (node (ref "C10") (pin "2") (pinfunction "2_2") (pintype "passive"))
      (node (ref "M1O2") (pin "P$1") (pinfunction "P$1_P$1") (pintype "bidirectional"))
      (node (ref "MOTOR1") (pin "8") (pinfunction "P$4_8") (pintype "bidirectional"))
      (node (ref "MOTOR1") (pin "9") (pinfunction "P$3_9") (pintype "bidirectional"))
      (node (ref "Q1") (pin "SOURCE") (pinfunction "P$2_SOURCE") (pintype "bidirectional"))
      (node (ref "Q4") (pin "DRAIN") (pinfunction "P$1_DRAIN") (pintype "bidirectional"))
      (node (ref "R9") (pin "2") (pinfunction "2_2") (pintype "passive"))
      (node (ref "U$4") (pin "SB") (pinfunction "SB_SB") (pintype "bidirectional"))
    )
    (net (code "27") (name "/M1O3") (class "Default")
      (node (ref "C11") (pin "2") (pinfunction "2_2") (pintype "passive"))
      (node (ref "M1O3") (pin "P$1") (pinfunction "P$1_P$1") (pintype "bidirectional"))
      (node (ref "MOTOR1") (pin "6") (pinfunction "P$6_6") (pintype "bidirectional"))
      (node (ref "MOTOR1") (pin "7") (pinfunction "P$5_7") (pintype "bidirectional"))
      (node (ref "Q2") (pin "SOURCE") (pinfunction "P$2_SOURCE") (pintype "bidirectional"))
      (node (ref "Q5") (pin "DRAIN") (pinfunction "P$1_DRAIN") (pintype "bidirectional"))
      (node (ref "R11") (pin "2") (pinfunction "2_2") (pintype "passive"))
      (node (ref "U$4") (pin "SC") (pinfunction "SC_SC") (pintype "bidirectional"))
    )
    (net (code "28") (name "/M1QA") (class "Default")
      (node (ref "QUAD1") (pin "2") (pinfunction "2_2") (pintype "passive"))
      (node (ref "U2") (pin "2") (pinfunction "PE0_2") (pintype "bidirectional"))
    )
    (net (code "29") (name "/M1QB") (class "Default")
      (node (ref "QUAD1") (pin "4") (pinfunction "4_4") (pintype "passive"))
      (node (ref "U2") (pin "3") (pinfunction "PE1_3") (pintype "bidirectional"))
    )
    (net (code "30") (name "/M2H1") (class "Default")
      (node (ref "MOTOR2") (pin "3") (pinfunction "P$9_3") (pintype "bidirectional"))
      (node (ref "R66") (pin "1") (pinfunction "1_1") (pintype "passive"))
      (node (ref "U$1") (pin "HA") (pinfunction "HA_HA") (pintype "bidirectional"))
    )
    (net (code "31") (name "/M2H2") (class "Default")
      (node (ref "MOTOR2") (pin "4") (pinfunction "P$8_4") (pintype "bidirectional"))
      (node (ref "R67") (pin "1") (pinfunction "1_1") (pintype "passive"))
      (node (ref "U$1") (pin "HB") (pinfunction "HB_HB") (pintype "bidirectional"))
    )
    (net (code "32") (name "/M2H3") (class "Default")
      (node (ref "MOTOR2") (pin "2") (pinfunction "P$10_2") (pintype "bidirectional"))
      (node (ref "R65") (pin "1") (pinfunction "1_1") (pintype "passive"))
      (node (ref "U$1") (pin "HC") (pinfunction "HC_HC") (pintype "bidirectional"))
    )
    (net (code "33") (name "/M2O1") (class "Default")
      (node (ref "C18") (pin "2") (pinfunction "2_2") (pintype "passive"))
      (node (ref "M2O1") (pin "P$1") (pinfunction "P$1_P$1") (pintype "bidirectional"))
      (node (ref "MOTOR2") (pin "10") (pinfunction "P$2_10") (pintype "bidirectional"))
      (node (ref "MOTOR2") (pin "11") (pinfunction "P$1_11") (pintype "bidirectional"))
      (node (ref "Q12") (pin "DRAIN") (pinfunction "P$1_DRAIN") (pintype "bidirectional"))
      (node (ref "Q9") (pin "SOURCE") (pinfunction "P$2_SOURCE") (pintype "bidirectional"))
      (node (ref "R20") (pin "2") (pinfunction "2_2") (pintype "passive"))
      (node (ref "U$1") (pin "SA") (pinfunction "SA_SA") (pintype "bidirectional"))
    )
    (net (code "34") (name "/M2O2") (class "Default")
      (node (ref "C19") (pin "2") (pinfunction "2_2") (pintype "passive"))
      (node (ref "M2O2") (pin "P$1") (pinfunction "P$1_P$1") (pintype "bidirectional"))
      (node (ref "MOTOR2") (pin "8") (pinfunction "P$4_8") (pintype "bidirectional"))
      (node (ref "MOTOR2") (pin "9") (pinfunction "P$3_9") (pintype "bidirectional"))
      (node (ref "Q10") (pin "SOURCE") (pinfunction "P$2_SOURCE") (pintype "bidirectional"))
      (node (ref "Q13") (pin "DRAIN") (pinfunction "P$1_DRAIN") (pintype "bidirectional"))
      (node (ref "R22") (pin "2") (pinfunction "2_2") (pintype "passive"))
      (node (ref "U$1") (pin "SB") (pinfunction "SB_SB") (pintype "bidirectional"))
    )
    (net (code "35") (name "/M2O3") (class "Default")
      (node (ref "C20") (pin "2") (pinfunction "2_2") (pintype "passive"))
      (node (ref "M2O3") (pin "P$1") (pinfunction "P$1_P$1") (pintype "bidirectional"))
      (node (ref "MOTOR2") (pin "6") (pinfunction "P$6_6") (pintype "bidirectional"))
      (node (ref "MOTOR2") (pin "7") (pinfunction "P$5_7") (pintype "bidirectional"))
      (node (ref "Q11") (pin "SOURCE") (pinfunction "P$2_SOURCE") (pintype "bidirectional"))
      (node (ref "Q14") (pin "DRAIN") (pinfunction "P$1_DRAIN") (pintype "bidirectional"))
      (node (ref "R24") (pin "2") (pinfunction "2_2") (pintype "passive"))
      (node (ref "U$1") (pin "SC") (pinfunction "SC_SC") (pintype "bidirectional"))
    )
    (net (code "36") (name "/M2QA") (class "Default")
      (node (ref "QUAD2") (pin "2") (pinfunction "2_2") (pintype "passive"))
      (node (ref "U2") (pin "4") (pinfunction "PE2_4") (pintype "bidirectional"))
    )
    (net (code "37") (name "/M2QB") (class "Default")
      (node (ref "QUAD2") (pin "4") (pinfunction "4_4") (pintype "passive"))
      (node (ref "U2") (pin "5") (pinfunction "PE3_5") (pintype "bidirectional"))
    )
    (net (code "38") (name "/M3H1") (class "Default")
      (node (ref "MOTOR3") (pin "3") (pinfunction "P$9_3") (pintype "bidirectional"))
      (node (ref "R72") (pin "1") (pinfunction "1_1") (pintype "passive"))
      (node (ref "U$2") (pin "HA") (pinfunction "HA_HA") (pintype "bidirectional"))
    )
    (net (code "39") (name "/M3H2") (class "Default")
      (node (ref "MOTOR3") (pin "4") (pinfunction "P$8_4") (pintype "bidirectional"))
      (node (ref "R73") (pin "1") (pinfunction "1_1") (pintype "passive"))
      (node (ref "U$2") (pin "HB") (pinfunction "HB_HB") (pintype "bidirectional"))
    )
    (net (code "40") (name "/M3H3") (class "Default")
      (node (ref "MOTOR3") (pin "2") (pinfunction "P$10_2") (pintype "bidirectional"))
      (node (ref "R71") (pin "1") (pinfunction "1_1") (pintype "passive"))
      (node (ref "U$2") (pin "HC") (pinfunction "HC_HC") (pintype "bidirectional"))
    )
    (net (code "41") (name "/M3O1") (class "Default")
      (node (ref "C27") (pin "2") (pinfunction "2_2") (pintype "passive"))
      (node (ref "M3O1") (pin "P$1") (pinfunction "P$1_P$1") (pintype "bidirectional"))
      (node (ref "MOTOR3") (pin "10") (pinfunction "P$2_10") (pintype "bidirectional"))
      (node (ref "MOTOR3") (pin "11") (pinfunction "P$1_11") (pintype "bidirectional"))
      (node (ref "Q17") (pin "SOURCE") (pinfunction "P$2_SOURCE") (pintype "bidirectional"))
      (node (ref "Q20") (pin "DRAIN") (pinfunction "P$1_DRAIN") (pintype "bidirectional"))
      (node (ref "R33") (pin "2") (pinfunction "2_2") (pintype "passive"))
      (node (ref "U$2") (pin "SA") (pinfunction "SA_SA") (pintype "bidirectional"))
    )
    (net (code "42") (name "/M3O2") (class "Default")
      (node (ref "C28") (pin "2") (pinfunction "2_2") (pintype "passive"))
      (node (ref "M3O2") (pin "P$1") (pinfunction "P$1_P$1") (pintype "bidirectional"))
      (node (ref "MOTOR3") (pin "8") (pinfunction "P$4_8") (pintype "bidirectional"))
      (node (ref "MOTOR3") (pin "9") (pinfunction "P$3_9") (pintype "bidirectional"))
      (node (ref "Q18") (pin "SOURCE") (pinfunction "P$2_SOURCE") (pintype "bidirectional"))
      (node (ref "Q21") (pin "DRAIN") (pinfunction "P$1_DRAIN") (pintype "bidirectional"))
      (node (ref "R35") (pin "2") (pinfunction "2_2") (pintype "passive"))
      (node (ref "U$2") (pin "SB") (pinfunction "SB_SB") (pintype "bidirectional"))
    )
    (net (code "43") (name "/M3O3") (class "Default")
      (node (ref "C29") (pin "2") (pinfunction "2_2") (pintype "passive"))
      (node (ref "M3O3") (pin "P$1") (pinfunction "P$1_P$1") (pintype "bidirectional"))
      (node (ref "MOTOR3") (pin "6") (pinfunction "P$6_6") (pintype "bidirectional"))
      (node (ref "MOTOR3") (pin "7") (pinfunction "P$5_7") (pintype "bidirectional"))
      (node (ref "Q19") (pin "SOURCE") (pinfunction "P$2_SOURCE") (pintype "bidirectional"))
      (node (ref "Q22") (pin "DRAIN") (pinfunction "P$1_DRAIN") (pintype "bidirectional"))
      (node (ref "R37") (pin "2") (pinfunction "2_2") (pintype "passive"))
      (node (ref "U$2") (pin "SC") (pinfunction "SC_SC") (pintype "bidirectional"))
    )
    (net (code "44") (name "/M3QA") (class "Default")
      (node (ref "QUAD3") (pin "2") (pinfunction "2_2") (pintype "passive"))
      (node (ref "U2") (pin "6") (pinfunction "PE4_6") (pintype "bidirectional"))
    )
    (net (code "45") (name "/M3QB") (class "Default")
      (node (ref "QUAD3") (pin "4") (pinfunction "4_4") (pintype "passive"))
      (node (ref "U2") (pin "7") (pinfunction "PE5_7") (pintype "bidirectional"))
    )
    (net (code "46") (name "/M4H1") (class "Default")
      (node (ref "MOTOR4") (pin "3") (pinfunction "P$9_3") (pintype "bidirectional"))
      (node (ref "R69") (pin "1") (pinfunction "1_1") (pintype "passive"))
      (node (ref "U$3") (pin "HA") (pinfunction "HA_HA") (pintype "bidirectional"))
    )
    (net (code "47") (name "/M4H2") (class "Default")
      (node (ref "MOTOR4") (pin "4") (pinfunction "P$8_4") (pintype "bidirectional"))
      (node (ref "R70") (pin "1") (pinfunction "1_1") (pintype "passive"))
      (node (ref "U$3") (pin "HB") (pinfunction "HB_HB") (pintype "bidirectional"))
    )
    (net (code "48") (name "/M4H3") (class "Default")
      (node (ref "MOTOR4") (pin "2") (pinfunction "P$10_2") (pintype "bidirectional"))
      (node (ref "R68") (pin "1") (pinfunction "1_1") (pintype "passive"))
      (node (ref "U$3") (pin "HC") (pinfunction "HC_HC") (pintype "bidirectional"))
    )
    (net (code "49") (name "/M4O1") (class "Default")
      (node (ref "C36") (pin "2") (pinfunction "2_2") (pintype "passive"))
      (node (ref "M4O1") (pin "P$1") (pinfunction "P$1_P$1") (pintype "bidirectional"))
      (node (ref "MOTOR4") (pin "10") (pinfunction "P$2_10") (pintype "bidirectional"))
      (node (ref "MOTOR4") (pin "11") (pinfunction "P$1_11") (pintype "bidirectional"))
      (node (ref "Q25") (pin "SOURCE") (pinfunction "P$2_SOURCE") (pintype "bidirectional"))
      (node (ref "Q28") (pin "DRAIN") (pinfunction "P$1_DRAIN") (pintype "bidirectional"))
      (node (ref "R46") (pin "2") (pinfunction "2_2") (pintype "passive"))
      (node (ref "U$3") (pin "SA") (pinfunction "SA_SA") (pintype "bidirectional"))
    )
    (net (code "50") (name "/M4O2") (class "Default")
      (node (ref "C37") (pin "2") (pinfunction "2_2") (pintype "passive"))
      (node (ref "M4O2") (pin "P$1") (pinfunction "P$1_P$1") (pintype "bidirectional"))
      (node (ref "MOTOR4") (pin "8") (pinfunction "P$4_8") (pintype "bidirectional"))
      (node (ref "MOTOR4") (pin "9") (pinfunction "P$3_9") (pintype "bidirectional"))
      (node (ref "Q26") (pin "SOURCE") (pinfunction "P$2_SOURCE") (pintype "bidirectional"))
      (node (ref "Q29") (pin "DRAIN") (pinfunction "P$1_DRAIN") (pintype "bidirectional"))
      (node (ref "R48") (pin "2") (pinfunction "2_2") (pintype "passive"))
      (node (ref "U$3") (pin "SB") (pinfunction "SB_SB") (pintype "bidirectional"))
    )
    (net (code "51") (name "/M4O3") (class "Default")
      (node (ref "C38") (pin "2") (pinfunction "2_2") (pintype "passive"))
      (node (ref "M4O3") (pin "P$1") (pinfunction "P$1_P$1") (pintype "bidirectional"))
      (node (ref "MOTOR4") (pin "6") (pinfunction "P$6_6") (pintype "bidirectional"))
      (node (ref "MOTOR4") (pin "7") (pinfunction "P$5_7") (pintype "bidirectional"))
      (node (ref "Q27") (pin "SOURCE") (pinfunction "P$2_SOURCE") (pintype "bidirectional"))
      (node (ref "Q30") (pin "DRAIN") (pinfunction "P$1_DRAIN") (pintype "bidirectional"))
      (node (ref "R50") (pin "2") (pinfunction "2_2") (pintype "passive"))
      (node (ref "U$3") (pin "SC") (pinfunction "SC_SC") (pintype "bidirectional"))
    )
    (net (code "52") (name "/M4QA") (class "Default")
      (node (ref "QUAD4") (pin "2") (pinfunction "2_2") (pintype "passive"))
      (node (ref "U2") (pin "8") (pinfunction "PE6_8") (pintype "bidirectional"))
    )
    (net (code "53") (name "/M4QB") (class "Default")
      (node (ref "QUAD4") (pin "4") (pinfunction "4_4") (pintype "passive"))
      (node (ref "U2") (pin "9") (pinfunction "PE7_9") (pintype "bidirectional"))
    )
    (net (code "54") (name "/MISO") (class "Default")
      (node (ref "JP1") (pin "9") (pinfunction "9_9") (pintype "passive"))
      (node (ref "R3") (pin "1") (pinfunction "1_1") (pintype "passive"))
      (node (ref "U2") (pin "13") (pinfunction "PB3_13") (pintype "bidirectional"))
    )
    (net (code "55") (name "/MOSI") (class "Default")
      (node (ref "JP1") (pin "1") (pinfunction "1_1") (pintype "passive"))
      (node (ref "R2") (pin "1") (pinfunction "1_1") (pintype "passive"))
      (node (ref "U2") (pin "12") (pinfunction "PB2_12") (pintype "bidirectional"))
    )
    (net (code "56") (name "/O2") (class "Default")
      (node (ref "LSS2") (pin "P$1") (pinfunction "P$1_P$1") (pintype "bidirectional"))
      (node (ref "Q12") (pin "SOURCE") (pinfunction "P$2_SOURCE") (pintype "bidirectional"))
      (node (ref "Q13") (pin "SOURCE") (pinfunction "P$2_SOURCE") (pintype "bidirectional"))
      (node (ref "Q14") (pin "SOURCE") (pinfunction "P$2_SOURCE") (pintype "bidirectional"))
      (node (ref "R28") (pin "2") (pinfunction "2_2") (pintype "passive"))
      (node (ref "R29") (pin "2") (pinfunction "2_2") (pintype "passive"))
      (node (ref "R30") (pin "2") (pinfunction "2_2") (pintype "passive"))
      (node (ref "R60") (pin "1") (pinfunction "1_1") (pintype "passive"))
      (node (ref "RSENSE2") (pin "2") (pinfunction "2_2") (pintype "passive"))
      (node (ref "U$1") (pin "LSS") (pinfunction "LSS_LSS") (pintype "bidirectional"))
    )
    (net (code "57") (name "/O3") (class "Default")
      (node (ref "LSS3") (pin "P$1") (pinfunction "P$1_P$1") (pintype "bidirectional"))
      (node (ref "Q20") (pin "SOURCE") (pinfunction "P$2_SOURCE") (pintype "bidirectional"))
      (node (ref "Q21") (pin "SOURCE") (pinfunction "P$2_SOURCE") (pintype "bidirectional"))
      (node (ref "Q22") (pin "SOURCE") (pinfunction "P$2_SOURCE") (pintype "bidirectional"))
      (node (ref "R109") (pin "1") (pinfunction "1_1") (pintype "passive"))
      (node (ref "R41") (pin "2") (pinfunction "2_2") (pintype "passive"))
      (node (ref "R42") (pin "2") (pinfunction "2_2") (pintype "passive"))
      (node (ref "R43") (pin "2") (pinfunction "2_2") (pintype "passive"))
      (node (ref "RSENSE3") (pin "2") (pinfunction "2_2") (pintype "passive"))
      (node (ref "U$2") (pin "LSS") (pinfunction "LSS_LSS") (pintype "bidirectional"))
    )
    (net (code "58") (name "/O4") (class "Default")
      (node (ref "LSS4") (pin "P$1") (pinfunction "P$1_P$1") (pintype "bidirectional"))
      (node (ref "Q28") (pin "SOURCE") (pinfunction "P$2_SOURCE") (pintype "bidirectional"))
      (node (ref "Q29") (pin "SOURCE") (pinfunction "P$2_SOURCE") (pintype "bidirectional"))
      (node (ref "Q30") (pin "SOURCE") (pinfunction "P$2_SOURCE") (pintype "bidirectional"))
      (node (ref "R54") (pin "2") (pinfunction "2_2") (pintype "passive"))
      (node (ref "R55") (pin "2") (pinfunction "2_2") (pintype "passive"))
      (node (ref "R56") (pin "2") (pinfunction "2_2") (pintype "passive"))
      (node (ref "R90") (pin "1") (pinfunction "1_1") (pintype "passive"))
      (node (ref "RSENSE4") (pin "2") (pinfunction "2_2") (pintype "passive"))
      (node (ref "U$3") (pin "LSS") (pinfunction "LSS_LSS") (pintype "bidirectional"))
    )
    (net (code "59") (name "/PWM1") (class "Default")
      (node (ref "R77") (pin "1") (pinfunction "1_1") (pintype "passive"))
      (node (ref "U2") (pin "14") (pinfunction "PB4_14") (pintype "bidirectional"))
    )
    (net (code "60") (name "/PWM2") (class "Default")
      (node (ref "R57") (pin "1") (pinfunction "1_1") (pintype "passive"))
      (node (ref "U2") (pin "15") (pinfunction "PB5_15") (pintype "bidirectional"))
    )
    (net (code "61") (name "/PWM3") (class "Default")
      (node (ref "R59") (pin "1") (pinfunction "1_1") (pintype "passive"))
      (node (ref "U2") (pin "16") (pinfunction "PB6_16") (pintype "bidirectional"))
    )
    (net (code "62") (name "/PWM4") (class "Default")
      (node (ref "R58") (pin "1") (pinfunction "1_1") (pintype "passive"))
      (node (ref "U2") (pin "17") (pinfunction "PB7_17") (pintype "bidirectional"))
    )
    (net (code "63") (name "/RESET") (class "Default")
      (node (ref "JP1") (pin "5") (pinfunction "5_5") (pintype "passive"))
      (node (ref "R113") (pin "1") (pinfunction "1_1") (pintype "passive"))
      (node (ref "S1") (pin "A2") (pinfunction "1_A2") (pintype "passive"))
      (node (ref "U2") (pin "20") (pinfunction "~{RESET/PG5}_20") (pintype "bidirectional"))
    )
    (net (code "64") (name "/SCK") (class "Default")
      (node (ref "JP1") (pin "7") (pinfunction "7_7") (pintype "passive"))
      (node (ref "R4") (pin "1") (pinfunction "1_1") (pintype "passive"))
      (node (ref "U2") (pin "11") (pinfunction "PB1_11") (pintype "bidirectional"))
    )
    (net (code "65") (name "/SENSE1") (class "Default")
      (node (ref "C47") (pin "1") (pinfunction "1_1") (pintype "passive"))
      (node (ref "COMP1") (pin "3") (pinfunction "IN-_3") (pintype "input"))
      (node (ref "OP1") (pin "1") (pinfunction "OUT_1") (pintype "output"))
      (node (ref "R89") (pin "2") (pinfunction "2_2") (pintype "passive"))
      (node (ref "SENSE1") (pin "P$1") (pinfunction "P$1_P$1") (pintype "bidirectional"))
      (node (ref "U2") (pin "61") (pinfunction "PF0_61") (pintype "bidirectional"))
    )
    (net (code "66") (name "/SENSE2") (class "Default")
      (node (ref "C1") (pin "1") (pinfunction "1_1") (pintype "passive"))
      (node (ref "COMP2") (pin "3") (pinfunction "IN-_3") (pintype "input"))
      (node (ref "OP2") (pin "1") (pinfunction "OUT_1") (pintype "output"))
      (node (ref "R86") (pin "2") (pinfunction "2_2") (pintype "passive"))
      (node (ref "SENSE2") (pin "P$1") (pinfunction "P$1_P$1") (pintype "bidirectional"))
      (node (ref "U2") (pin "60") (pinfunction "PF1_60") (pintype "bidirectional"))
    )
    (net (code "67") (name "/SENSE3") (class "Default")
      (node (ref "C49") (pin "1") (pinfunction "1_1") (pintype "passive"))
      (node (ref "COMP3") (pin "3") (pinfunction "IN-_3") (pintype "input"))
      (node (ref "OP3") (pin "1") (pinfunction "OUT_1") (pintype "output"))
      (node (ref "R112") (pin "2") (pinfunction "2_2") (pintype "passive"))
      (node (ref "SENSE3") (pin "P$1") (pinfunction "P$1_P$1") (pintype "bidirectional"))
      (node (ref "U2") (pin "59") (pinfunction "PF2_59") (pintype "bidirectional"))
    )
    (net (code "68") (name "/SENSE4") (class "Default")
      (node (ref "C48") (pin "1") (pinfunction "1_1") (pintype "passive"))
      (node (ref "COMP4") (pin "3") (pinfunction "IN-_3") (pintype "input"))
      (node (ref "OP4") (pin "1") (pinfunction "OUT_1") (pintype "output"))
      (node (ref "R108") (pin "2") (pinfunction "2_2") (pintype "passive"))
      (node (ref "SENSE4") (pin "P$1") (pinfunction "P$1_P$1") (pintype "bidirectional"))
      (node (ref "U2") (pin "58") (pinfunction "PF3_58") (pintype "bidirectional"))
    )
    (net (code "69") (name "/SS_E1") (class "Default")
      (node (ref "SPI_HEADER") (pin "6") (pinfunction "6_6") (pintype "passive"))
    )
    (net (code "70") (name "/SS_E2") (class "Default")
      (node (ref "SPI_HEADER") (pin "7") (pinfunction "7_7") (pintype "passive"))
    )
    (net (code "71") (name "/SS_E3") (class "Default")
      (node (ref "SPI_HEADER") (pin "8") (pinfunction "8_8") (pintype "passive"))
    )
    (net (code "72") (name "/SS_K") (class "Default")
      (node (ref "SPI_HEADER") (pin "5") (pinfunction "5_5") (pintype "passive"))
    )
    (net (code "73") (name "/SS_M") (class "Default")
      (node (ref "SPI_HEADER") (pin "4") (pinfunction "4_4") (pintype "passive"))
      (node (ref "U2") (pin "10") (pinfunction "PB0_10") (pintype "bidirectional"))
    )
    (net (code "74") (name "/TSENSE1") (class "Default")
      (node (ref "U$5") (pin "2") (pinfunction "VO_2") (pintype "bidirectional"))
      (node (ref "U2") (pin "57") (pinfunction "PF4_57") (pintype "bidirectional"))
    )
    (net (code "75") (name "/TSENSE2") (class "Default")
      (node (ref "U$6") (pin "2") (pinfunction "VO_2") (pintype "bidirectional"))
      (node (ref "U2") (pin "56") (pinfunction "PF5_56") (pintype "bidirectional"))
    )
    (net (code "76") (name "/TSENSE3") (class "Default")
      (node (ref "U$8") (pin "2") (pinfunction "VO_2") (pintype "bidirectional"))
      (node (ref "U2") (pin "55") (pinfunction "PF6_55") (pintype "bidirectional"))
    )
    (net (code "77") (name "/TSENSE4") (class "Default")
      (node (ref "U$7") (pin "2") (pinfunction "VO_2") (pintype "bidirectional"))
      (node (ref "U2") (pin "54") (pinfunction "PF7_54") (pintype "bidirectional"))
    )
    (net (code "78") (name "GND") (class "Default")
      (node (ref "C13") (pin "2") (pinfunction "2_2") (pintype "passive"))
      (node (ref "C14") (pin "1") (pinfunction "1_1") (pintype "passive"))
      (node (ref "C15") (pin "1") (pinfunction "1_1") (pintype "passive"))
      (node (ref "C22") (pin "2") (pinfunction "2_2") (pintype "passive"))
      (node (ref "C23") (pin "1") (pinfunction "1_1") (pintype "passive"))
      (node (ref "C24") (pin "1") (pinfunction "1_1") (pintype "passive"))
      (node (ref "C31") (pin "2") (pinfunction "2_2") (pintype "passive"))
      (node (ref "C32") (pin "1") (pinfunction "1_1") (pintype "passive"))
      (node (ref "C33") (pin "1") (pinfunction "1_1") (pintype "passive"))
      (node (ref "C39") (pin "1") (pinfunction "1_1") (pintype "passive"))
      (node (ref "C4") (pin "2") (pinfunction "2_2") (pintype "passive"))
      (node (ref "C40") (pin "1") (pinfunction "1_1") (pintype "passive"))
      (node (ref "C45") (pin "2") (pinfunction "2_2") (pintype "passive"))
      (node (ref "C46") (pin "2") (pinfunction "2_2") (pintype "passive"))
      (node (ref "C5") (pin "1") (pinfunction "1_1") (pintype "passive"))
      (node (ref "C51") (pin "1") (pinfunction "1_1") (pintype "passive"))
      (node (ref "C52") (pin "1") (pinfunction "1_1") (pintype "passive"))
      (node (ref "C53") (pin "1") (pinfunction "1_1") (pintype "passive"))
      (node (ref "C54") (pin "1") (pinfunction "1_1") (pintype "passive"))
      (node (ref "C55") (pin "1") (pinfunction "1_1") (pintype "passive"))
      (node (ref "C56") (pin "1") (pinfunction "1_1") (pintype "passive"))
      (node (ref "C57") (pin "1") (pinfunction "1_1") (pintype "passive"))
      (node (ref "C58") (pin "1") (pinfunction "1_1") (pintype "passive"))
      (node (ref "C59") (pin "2") (pinfunction "2_2") (pintype "passive"))
      (node (ref "C6") (pin "1") (pinfunction "1_1") (pintype "passive"))
      (node (ref "C60") (pin "2") (pinfunction "2_2") (pintype "passive"))
      (node (ref "C61") (pin "2") (pinfunction "2_2") (pintype "passive"))
      (node (ref "C62") (pin "2") (pinfunction "2_2") (pintype "passive"))
      (node (ref "C63") (pin "2") (pinfunction "2_2") (pintype "passive"))
      (node (ref "C64") (pin "2") (pinfunction "2_2") (pintype "passive"))
      (node (ref "C65") (pin "1") (pinfunction "1_1") (pintype "passive"))
      (node (ref "C66") (pin "1") (pinfunction "1_1") (pintype "passive"))
      (node (ref "C67") (pin "1") (pinfunction "1_1") (pintype "passive"))
      (node (ref "C68") (pin "1") (pinfunction "1_1") (pintype "passive"))
      (node (ref "C69") (pin "2") (pinfunction "2_2") (pintype "passive"))
      (node (ref "C70") (pin "1") (pinfunction "1_1") (pintype "passive"))
      (node (ref "C71") (pin "2") (pinfunction "2_2") (pintype "passive"))
      (node (ref "C72") (pin "1") (pinfunction "1_1") (pintype "passive"))
      (node (ref "COMP1") (pin "2") (pinfunction "V-_2") (pintype "power_in"))
      (node (ref "COMP2") (pin "2") (pinfunction "V-_2") (pintype "power_in"))
      (node (ref "COMP3") (pin "2") (pinfunction "V-_2") (pintype "power_in"))
      (node (ref "COMP4") (pin "2") (pinfunction "V-_2") (pintype "power_in"))
      (node (ref "JP1") (pin "10") (pinfunction "10_10") (pintype "passive"))
      (node (ref "JP1") (pin "4") (pinfunction "4_4") (pintype "passive"))
      (node (ref "JP1") (pin "6") (pinfunction "6_6") (pintype "passive"))
      (node (ref "JP1") (pin "8") (pinfunction "8_8") (pintype "passive"))
      (node (ref "LED11") (pin "C") (pinfunction "C_C") (pintype "passive"))
      (node (ref "LED13") (pin "C") (pinfunction "C_C") (pintype "passive"))
      (node (ref "LED15") (pin "C") (pinfunction "C_C") (pintype "passive"))
      (node (ref "LED9") (pin "C") (pinfunction "C_C") (pintype "passive"))
      (node (ref "LOGIC_HEADER") (pin "1") (pinfunction "1_1") (pintype "passive"))
      (node (ref "LOGIC_HEADER") (pin "2") (pinfunction "2_2") (pintype "passive"))
      (node (ref "LOGIC_HEADER") (pin "3") (pinfunction "3_3") (pintype "passive"))
      (node (ref "LOGIC_HEADER") (pin "4") (pinfunction "4_4") (pintype "passive"))
      (node (ref "MOTOR1") (pin "5") (pinfunction "P$7_5") (pintype "bidirectional"))
      (node (ref "MOTOR2") (pin "5") (pinfunction "P$7_5") (pintype "bidirectional"))
      (node (ref "MOTOR3") (pin "5") (pinfunction "P$7_5") (pintype "bidirectional"))
      (node (ref "MOTOR4") (pin "5") (pinfunction "P$7_5") (pintype "bidirectional"))
      (node (ref "OP1") (pin "2") (pinfunction "V-_2") (pintype "power_in"))
      (node (ref "OP2") (pin "2") (pinfunction "V-_2") (pintype "power_in"))
      (node (ref "OP3") (pin "2") (pinfunction "V-_2") (pintype "power_in"))
      (node (ref "OP4") (pin "2") (pinfunction "V-_2") (pintype "power_in"))
      (node (ref "QUAD1") (pin "3") (pinfunction "3_3") (pintype "passive"))
      (node (ref "QUAD2") (pin "3") (pinfunction "3_3") (pintype "passive"))
      (node (ref "QUAD3") (pin "3") (pinfunction "3_3") (pintype "passive"))
      (node (ref "QUAD4") (pin "3") (pinfunction "3_3") (pintype "passive"))
      (node (ref "R100") (pin "2") (pinfunction "2_2") (pintype "passive"))
      (node (ref "R104") (pin "1") (pinfunction "1_1") (pintype "passive"))
      (node (ref "R111") (pin "2") (pinfunction "2_2") (pintype "passive"))
      (node (ref "R18") (pin "2") (pinfunction "2_2") (pintype "passive"))
      (node (ref "R31") (pin "2") (pinfunction "2_2") (pintype "passive"))
      (node (ref "R44") (pin "2") (pinfunction "2_2") (pintype "passive"))
      (node (ref "R5") (pin "2") (pinfunction "2_2") (pintype "passive"))
      (node (ref "R76") (pin "2") (pinfunction "2_2") (pintype "passive"))
      (node (ref "R80") (pin "1") (pinfunction "1_1") (pintype "passive"))
      (node (ref "R83") (pin "2") (pinfunction "2_2") (pintype "passive"))
      (node (ref "R94") (pin "1") (pinfunction "1_1") (pintype "passive"))
      (node (ref "R96") (pin "1") (pinfunction "1_1") (pintype "passive"))
      (node (ref "S1") (pin "B2") (pinfunction "2_B2") (pintype "passive"))
      (node (ref "U$1") (pin "GND") (pinfunction "GND_GND") (pintype "bidirectional"))
      (node (ref "U$1") (pin "PAD") (pinfunction "PAD_PAD") (pintype "bidirectional"))
      (node (ref "U$2") (pin "GND") (pinfunction "GND_GND") (pintype "bidirectional"))
      (node (ref "U$2") (pin "PAD") (pinfunction "PAD_PAD") (pintype "bidirectional"))
      (node (ref "U$3") (pin "GND") (pinfunction "GND_GND") (pintype "bidirectional"))
      (node (ref "U$3") (pin "PAD") (pinfunction "PAD_PAD") (pintype "bidirectional"))
      (node (ref "U$4") (pin "GND") (pinfunction "GND_GND") (pintype "bidirectional"))
      (node (ref "U$4") (pin "PAD") (pinfunction "PAD_PAD") (pintype "bidirectional"))
      (node (ref "U$5") (pin "3") (pinfunction "GND_3") (pintype "bidirectional"))
      (node (ref "U$6") (pin "3") (pinfunction "GND_3") (pintype "bidirectional"))
      (node (ref "U$7") (pin "3") (pinfunction "GND_3") (pintype "bidirectional"))
      (node (ref "U$8") (pin "3") (pinfunction "GND_3") (pintype "bidirectional"))
      (node (ref "U2") (pin "22") (pinfunction "GND_3_22") (pintype "passive"))
      (node (ref "U2") (pin "53") (pinfunction "GND_2_53") (pintype "passive"))
      (node (ref "U2") (pin "63") (pinfunction "GND_63") (pintype "passive"))
    )
    (net (code "79") (name "Net-(C3-Pad1)") (class "Default")
      (node (ref "C3") (pin "1") (pinfunction "1_1") (pintype "passive"))
      (node (ref "U$4") (pin "CP1") (pinfunction "CP1_CP1") (pintype "bidirectional"))
    )
    (net (code "80") (name "Net-(C3-Pad2)") (class "Default")
      (node (ref "C3") (pin "2") (pinfunction "2_2") (pintype "passive"))
      (node (ref "U$4") (pin "CP2") (pinfunction "CP2_CP2") (pintype "bidirectional"))
    )
    (net (code "81") (name "Net-(C5-Pad2)") (class "Default")
      (node (ref "C5") (pin "2") (pinfunction "2_2") (pintype "passive"))
      (node (ref "U$4") (pin "VREG") (pinfunction "VREG_VREG") (pintype "bidirectional"))
    )
    (net (code "82") (name "Net-(C9-Pad1)") (class "Default")
      (node (ref "C9") (pin "1") (pinfunction "1_1") (pintype "passive"))
      (node (ref "U$4") (pin "CA") (pinfunction "CA_CA") (pintype "bidirectional"))
    )
    (net (code "83") (name "Net-(C10-Pad1)") (class "Default")
      (node (ref "C10") (pin "1") (pinfunction "1_1") (pintype "passive"))
      (node (ref "U$4") (pin "CB") (pinfunction "CB_CB") (pintype "bidirectional"))
    )
    (net (code "84") (name "Net-(C11-Pad1)") (class "Default")
      (node (ref "C11") (pin "1") (pinfunction "1_1") (pintype "passive"))
      (node (ref "U$4") (pin "CC") (pinfunction "CC_CC") (pintype "bidirectional"))
    )
    (net (code "85") (name "Net-(C12-Pad1)") (class "Default")
      (node (ref "C12") (pin "1") (pinfunction "1_1") (pintype "passive"))
      (node (ref "U$1") (pin "CP1") (pinfunction "CP1_CP1") (pintype "bidirectional"))
    )
    (net (code "86") (name "Net-(C12-Pad2)") (class "Default")
      (node (ref "C12") (pin "2") (pinfunction "2_2") (pintype "passive"))
      (node (ref "U$1") (pin "CP2") (pinfunction "CP2_CP2") (pintype "bidirectional"))
    )
    (net (code "87") (name "Net-(C14-Pad2)") (class "Default")
      (node (ref "C14") (pin "2") (pinfunction "2_2") (pintype "passive"))
      (node (ref "U$1") (pin "VREG") (pinfunction "VREG_VREG") (pintype "bidirectional"))
    )
    (net (code "88") (name "Net-(C18-Pad1)") (class "Default")
      (node (ref "C18") (pin "1") (pinfunction "1_1") (pintype "passive"))
      (node (ref "U$1") (pin "CA") (pinfunction "CA_CA") (pintype "bidirectional"))
    )
    (net (code "89") (name "Net-(C19-Pad1)") (class "Default")
      (node (ref "C19") (pin "1") (pinfunction "1_1") (pintype "passive"))
      (node (ref "U$1") (pin "CB") (pinfunction "CB_CB") (pintype "bidirectional"))
    )
    (net (code "90") (name "Net-(C20-Pad1)") (class "Default")
      (node (ref "C20") (pin "1") (pinfunction "1_1") (pintype "passive"))
      (node (ref "U$1") (pin "CC") (pinfunction "CC_CC") (pintype "bidirectional"))
    )
    (net (code "91") (name "Net-(C21-Pad1)") (class "Default")
      (node (ref "C21") (pin "1") (pinfunction "1_1") (pintype "passive"))
      (node (ref "U$2") (pin "CP1") (pinfunction "CP1_CP1") (pintype "bidirectional"))
    )
    (net (code "92") (name "Net-(C21-Pad2)") (class "Default")
      (node (ref "C21") (pin "2") (pinfunction "2_2") (pintype "passive"))
      (node (ref "U$2") (pin "CP2") (pinfunction "CP2_CP2") (pintype "bidirectional"))
    )
    (net (code "93") (name "Net-(C23-Pad2)") (class "Default")
      (node (ref "C23") (pin "2") (pinfunction "2_2") (pintype "passive"))
      (node (ref "U$2") (pin "VREG") (pinfunction "VREG_VREG") (pintype "bidirectional"))
    )
    (net (code "94") (name "Net-(C27-Pad1)") (class "Default")
      (node (ref "C27") (pin "1") (pinfunction "1_1") (pintype "passive"))
      (node (ref "U$2") (pin "CA") (pinfunction "CA_CA") (pintype "bidirectional"))
    )
    (net (code "95") (name "Net-(C28-Pad1)") (class "Default")
      (node (ref "C28") (pin "1") (pinfunction "1_1") (pintype "passive"))
      (node (ref "U$2") (pin "CB") (pinfunction "CB_CB") (pintype "bidirectional"))
    )
    (net (code "96") (name "Net-(C29-Pad1)") (class "Default")
      (node (ref "C29") (pin "1") (pinfunction "1_1") (pintype "passive"))
      (node (ref "U$2") (pin "CC") (pinfunction "CC_CC") (pintype "bidirectional"))
    )
    (net (code "97") (name "Net-(C30-Pad1)") (class "Default")
      (node (ref "C30") (pin "1") (pinfunction "1_1") (pintype "passive"))
      (node (ref "U$3") (pin "CP1") (pinfunction "CP1_CP1") (pintype "bidirectional"))
    )
    (net (code "98") (name "Net-(C30-Pad2)") (class "Default")
      (node (ref "C30") (pin "2") (pinfunction "2_2") (pintype "passive"))
      (node (ref "U$3") (pin "CP2") (pinfunction "CP2_CP2") (pintype "bidirectional"))
    )
    (net (code "99") (name "Net-(C32-Pad2)") (class "Default")
      (node (ref "C32") (pin "2") (pinfunction "2_2") (pintype "passive"))
      (node (ref "U$3") (pin "VREG") (pinfunction "VREG_VREG") (pintype "bidirectional"))
    )
    (net (code "100") (name "Net-(C36-Pad1)") (class "Default")
      (node (ref "C36") (pin "1") (pinfunction "1_1") (pintype "passive"))
      (node (ref "U$3") (pin "CA") (pinfunction "CA_CA") (pintype "bidirectional"))
    )
    (net (code "101") (name "Net-(C37-Pad1)") (class "Default")
      (node (ref "C37") (pin "1") (pinfunction "1_1") (pintype "passive"))
      (node (ref "U$3") (pin "CB") (pinfunction "CB_CB") (pintype "bidirectional"))
    )
    (net (code "102") (name "Net-(C38-Pad1)") (class "Default")
      (node (ref "C38") (pin "1") (pinfunction "1_1") (pintype "passive"))
      (node (ref "U$3") (pin "CC") (pinfunction "CC_CC") (pintype "bidirectional"))
    )
    (net (code "103") (name "Net-(COMP1-IN+)") (class "Default")
      (node (ref "COMP1") (pin "1") (pinfunction "IN+_1") (pintype "input"))
      (node (ref "R114") (pin "2") (pinfunction "2_2") (pintype "passive"))
      (node (ref "R93") (pin "1") (pinfunction "1_1") (pintype "passive"))
      (node (ref "R94") (pin "2") (pinfunction "2_2") (pintype "passive"))
    )
    (net (code "104") (name "Net-(COMP2-IN+)") (class "Default")
      (node (ref "COMP2") (pin "1") (pinfunction "IN+_1") (pintype "input"))
      (node (ref "R115") (pin "2") (pinfunction "2_2") (pintype "passive"))
      (node (ref "R62") (pin "1") (pinfunction "1_1") (pintype "passive"))
      (node (ref "R80") (pin "2") (pinfunction "2_2") (pintype "passive"))
    )
    (net (code "105") (name "Net-(COMP3-IN+)") (class "Default")
      (node (ref "COMP3") (pin "1") (pinfunction "IN+_1") (pintype "input"))
      (node (ref "R102") (pin "1") (pinfunction "1_1") (pintype "passive"))
      (node (ref "R104") (pin "2") (pinfunction "2_2") (pintype "passive"))
      (node (ref "R116") (pin "2") (pinfunction "2_2") (pintype "passive"))
    )
    (net (code "106") (name "Net-(COMP4-IN+)") (class "Default")
      (node (ref "COMP4") (pin "1") (pinfunction "IN+_1") (pintype "input"))
      (node (ref "R117") (pin "2") (pinfunction "2_2") (pintype "passive"))
      (node (ref "R95") (pin "1") (pinfunction "1_1") (pintype "passive"))
      (node (ref "R96") (pin "2") (pinfunction "2_2") (pintype "passive"))
    )
    (net (code "107") (name "Net-(LED9-PadA)") (class "Default")
      (node (ref "LED9") (pin "A") (pinfunction "A_A") (pintype "passive"))
      (node (ref "R1") (pin "1") (pinfunction "1_1") (pintype "passive"))
    )
    (net (code "108") (name "Net-(LED11-PadA)") (class "Default")
      (node (ref "LED11") (pin "A") (pinfunction "A_A") (pintype "passive"))
      (node (ref "R99") (pin "1") (pinfunction "1_1") (pintype "passive"))
    )
    (net (code "109") (name "Net-(LED13-PadA)") (class "Default")
      (node (ref "LED13") (pin "A") (pinfunction "A_A") (pintype "passive"))
      (node (ref "R101") (pin "1") (pinfunction "1_1") (pintype "passive"))
    )
    (net (code "110") (name "Net-(LED15-PadA)") (class "Default")
      (node (ref "LED15") (pin "A") (pinfunction "A_A") (pintype "passive"))
      (node (ref "R103") (pin "1") (pinfunction "1_1") (pintype "passive"))
    )
    (net (code "111") (name "Net-(OP1-+IN)") (class "Default")
      (node (ref "C65") (pin "2") (pinfunction "2_2") (pintype "passive"))
      (node (ref "OP1") (pin "3") (pinfunction "+IN_3") (pintype "input"))
      (node (ref "R74") (pin "2") (pinfunction "2_2") (pintype "passive"))
      (node (ref "R76") (pin "1") (pinfunction "1_1") (pintype "passive"))
    )
    (net (code "112") (name "Net-(OP1--IN)") (class "Default")
      (node (ref "C47") (pin "2") (pinfunction "2_2") (pintype "passive"))
      (node (ref "OP1") (pin "4") (pinfunction "-IN_4") (pintype "input"))
      (node (ref "R75") (pin "2") (pinfunction "2_2") (pintype "passive"))
      (node (ref "R89") (pin "1") (pinfunction "1_1") (pintype "passive"))
    )
    (net (code "113") (name "Net-(OP2-+IN)") (class "Default")
      (node (ref "C66") (pin "2") (pinfunction "2_2") (pintype "passive"))
      (node (ref "OP2") (pin "3") (pinfunction "+IN_3") (pintype "input"))
      (node (ref "R60") (pin "2") (pinfunction "2_2") (pintype "passive"))
      (node (ref "R83") (pin "1") (pinfunction "1_1") (pintype "passive"))
    )
    (net (code "114") (name "Net-(OP2--IN)") (class "Default")
      (node (ref "C1") (pin "2") (pinfunction "2_2") (pintype "passive"))
      (node (ref "OP2") (pin "4") (pinfunction "-IN_4") (pintype "input"))
      (node (ref "R61") (pin "2") (pinfunction "2_2") (pintype "passive"))
      (node (ref "R86") (pin "1") (pinfunction "1_1") (pintype "passive"))
    )
    (net (code "115") (name "Net-(OP3-+IN)") (class "Default")
      (node (ref "C67") (pin "2") (pinfunction "2_2") (pintype "passive"))
      (node (ref "OP3") (pin "3") (pinfunction "+IN_3") (pintype "input"))
      (node (ref "R109") (pin "2") (pinfunction "2_2") (pintype "passive"))
      (node (ref "R111") (pin "1") (pinfunction "1_1") (pintype "passive"))
    )
    (net (code "116") (name "Net-(OP3--IN)") (class "Default")
      (node (ref "C49") (pin "2") (pinfunction "2_2") (pintype "passive"))
      (node (ref "OP3") (pin "4") (pinfunction "-IN_4") (pintype "input"))
      (node (ref "R110") (pin "2") (pinfunction "2_2") (pintype "passive"))
      (node (ref "R112") (pin "1") (pinfunction "1_1") (pintype "passive"))
    )
    (net (code "117") (name "Net-(OP4-+IN)") (class "Default")
      (node (ref "C68") (pin "2") (pinfunction "2_2") (pintype "passive"))
      (node (ref "OP4") (pin "3") (pinfunction "+IN_3") (pintype "input"))
      (node (ref "R100") (pin "1") (pinfunction "1_1") (pintype "passive"))
      (node (ref "R90") (pin "2") (pinfunction "2_2") (pintype "passive"))
    )
    (net (code "118") (name "Net-(OP4--IN)") (class "Default")
      (node (ref "C48") (pin "2") (pinfunction "2_2") (pintype "passive"))
      (node (ref "OP4") (pin "4") (pinfunction "-IN_4") (pintype "input"))
      (node (ref "R108") (pin "1") (pinfunction "1_1") (pintype "passive"))
      (node (ref "R98") (pin "2") (pinfunction "2_2") (pintype "passive"))
    )
    (net (code "119") (name "Net-(Q1-P$3)") (class "Default")
      (node (ref "Q1") (pin "GATE") (pinfunction "P$3_GATE") (pintype "bidirectional"))
      (node (ref "R8") (pin "2") (pinfunction "2_2") (pintype "passive"))
      (node (ref "R9") (pin "1") (pinfunction "1_1") (pintype "passive"))
    )
    (net (code "120") (name "Net-(Q2-P$3)") (class "Default")
      (node (ref "Q2") (pin "GATE") (pinfunction "P$3_GATE") (pintype "bidirectional"))
      (node (ref "R10") (pin "2") (pinfunction "2_2") (pintype "passive"))
      (node (ref "R11") (pin "1") (pinfunction "1_1") (pintype "passive"))
    )
    (net (code "121") (name "Net-(Q3-P$2)") (class "Default")
      (node (ref "LSS1") (pin "P$1") (pinfunction "P$1_P$1") (pintype "bidirectional"))
      (node (ref "Q3") (pin "SOURCE") (pinfunction "P$2_SOURCE") (pintype "bidirectional"))
      (node (ref "Q4") (pin "SOURCE") (pinfunction "P$2_SOURCE") (pintype "bidirectional"))
      (node (ref "Q5") (pin "SOURCE") (pinfunction "P$2_SOURCE") (pintype "bidirectional"))
      (node (ref "R15") (pin "2") (pinfunction "2_2") (pintype "passive"))
      (node (ref "R16") (pin "2") (pinfunction "2_2") (pintype "passive"))
      (node (ref "R17") (pin "2") (pinfunction "2_2") (pintype "passive"))
      (node (ref "R74") (pin "1") (pinfunction "1_1") (pintype "passive"))
      (node (ref "RSENSE1") (pin "2") (pinfunction "2_2") (pintype "passive"))
      (node (ref "U$4") (pin "LSS") (pinfunction "LSS_LSS") (pintype "bidirectional"))
    )
    (net (code "122") (name "Net-(Q3-P$3)") (class "Default")
      (node (ref "Q3") (pin "GATE") (pinfunction "P$3_GATE") (pintype "bidirectional"))
      (node (ref "R12") (pin "2") (pinfunction "2_2") (pintype "passive"))
      (node (ref "R15") (pin "1") (pinfunction "1_1") (pintype "passive"))
    )
    (net (code "123") (name "Net-(Q4-P$3)") (class "Default")
      (node (ref "Q4") (pin "GATE") (pinfunction "P$3_GATE") (pintype "bidirectional"))
      (node (ref "R13") (pin "2") (pinfunction "2_2") (pintype "passive"))
      (node (ref "R16") (pin "1") (pinfunction "1_1") (pintype "passive"))
    )
    (net (code "124") (name "Net-(Q5-P$3)") (class "Default")
      (node (ref "Q5") (pin "GATE") (pinfunction "P$3_GATE") (pintype "bidirectional"))
      (node (ref "R14") (pin "2") (pinfunction "2_2") (pintype "passive"))
      (node (ref "R17") (pin "1") (pinfunction "1_1") (pintype "passive"))
    )
    (net (code "125") (name "Net-(Q6-P$3)") (class "Default")
      (node (ref "Q6") (pin "GATE") (pinfunction "P$3_GATE") (pintype "bidirectional"))
      (node (ref "R6") (pin "2") (pinfunction "2_2") (pintype "passive"))
      (node (ref "R7") (pin "1") (pinfunction "1_1") (pintype "passive"))
    )
    (net (code "126") (name "Net-(Q9-P$3)") (class "Default")
      (node (ref "Q9") (pin "GATE") (pinfunction "P$3_GATE") (pintype "bidirectional"))
      (node (ref "R19") (pin "2") (pinfunction "2_2") (pintype "passive"))
      (node (ref "R20") (pin "1") (pinfunction "1_1") (pintype "passive"))
    )
    (net (code "127") (name "Net-(Q10-P$3)") (class "Default")
      (node (ref "Q10") (pin "GATE") (pinfunction "P$3_GATE") (pintype "bidirectional"))
      (node (ref "R21") (pin "2") (pinfunction "2_2") (pintype "passive"))
      (node (ref "R22") (pin "1") (pinfunction "1_1") (pintype "passive"))
    )
    (net (code "128") (name "Net-(Q11-P$3)") (class "Default")
      (node (ref "Q11") (pin "GATE") (pinfunction "P$3_GATE") (pintype "bidirectional"))
      (node (ref "R23") (pin "2") (pinfunction "2_2") (pintype "passive"))
      (node (ref "R24") (pin "1") (pinfunction "1_1") (pintype "passive"))
    )
    (net (code "129") (name "Net-(Q12-P$3)") (class "Default")
      (node (ref "Q12") (pin "GATE") (pinfunction "P$3_GATE") (pintype "bidirectional"))
      (node (ref "R25") (pin "2") (pinfunction "2_2") (pintype "passive"))
      (node (ref "R28") (pin "1") (pinfunction "1_1") (pintype "passive"))
    )
    (net (code "130") (name "Net-(Q13-P$3)") (class "Default")
      (node (ref "Q13") (pin "GATE") (pinfunction "P$3_GATE") (pintype "bidirectional"))
      (node (ref "R26") (pin "2") (pinfunction "2_2") (pintype "passive"))
      (node (ref "R29") (pin "1") (pinfunction "1_1") (pintype "passive"))
    )
    (net (code "131") (name "Net-(Q14-P$3)") (class "Default")
      (node (ref "Q14") (pin "GATE") (pinfunction "P$3_GATE") (pintype "bidirectional"))
      (node (ref "R27") (pin "2") (pinfunction "2_2") (pintype "passive"))
      (node (ref "R30") (pin "1") (pinfunction "1_1") (pintype "passive"))
    )
    (net (code "132") (name "Net-(Q17-P$3)") (class "Default")
      (node (ref "Q17") (pin "GATE") (pinfunction "P$3_GATE") (pintype "bidirectional"))
      (node (ref "R32") (pin "2") (pinfunction "2_2") (pintype "passive"))
      (node (ref "R33") (pin "1") (pinfunction "1_1") (pintype "passive"))
    )
    (net (code "133") (name "Net-(Q18-P$3)") (class "Default")
      (node (ref "Q18") (pin "GATE") (pinfunction "P$3_GATE") (pintype "bidirectional"))
      (node (ref "R34") (pin "2") (pinfunction "2_2") (pintype "passive"))
      (node (ref "R35") (pin "1") (pinfunction "1_1") (pintype "passive"))
    )
    (net (code "134") (name "Net-(Q19-P$3)") (class "Default")
      (node (ref "Q19") (pin "GATE") (pinfunction "P$3_GATE") (pintype "bidirectional"))
      (node (ref "R36") (pin "2") (pinfunction "2_2") (pintype "passive"))
      (node (ref "R37") (pin "1") (pinfunction "1_1") (pintype "passive"))
    )
    (net (code "135") (name "Net-(Q20-P$3)") (class "Default")
      (node (ref "Q20") (pin "GATE") (pinfunction "P$3_GATE") (pintype "bidirectional"))
      (node (ref "R38") (pin "2") (pinfunction "2_2") (pintype "passive"))
      (node (ref "R41") (pin "1") (pinfunction "1_1") (pintype "passive"))
    )
    (net (code "136") (name "Net-(Q21-P$3)") (class "Default")
      (node (ref "Q21") (pin "GATE") (pinfunction "P$3_GATE") (pintype "bidirectional"))
      (node (ref "R39") (pin "2") (pinfunction "2_2") (pintype "passive"))
      (node (ref "R42") (pin "1") (pinfunction "1_1") (pintype "passive"))
    )
    (net (code "137") (name "Net-(Q22-P$3)") (class "Default")
      (node (ref "Q22") (pin "GATE") (pinfunction "P$3_GATE") (pintype "bidirectional"))
      (node (ref "R40") (pin "2") (pinfunction "2_2") (pintype "passive"))
      (node (ref "R43") (pin "1") (pinfunction "1_1") (pintype "passive"))
    )
    (net (code "138") (name "Net-(Q25-P$3)") (class "Default")
      (node (ref "Q25") (pin "GATE") (pinfunction "P$3_GATE") (pintype "bidirectional"))
      (node (ref "R45") (pin "2") (pinfunction "2_2") (pintype "passive"))
      (node (ref "R46") (pin "1") (pinfunction "1_1") (pintype "passive"))
    )
    (net (code "139") (name "Net-(Q26-P$3)") (class "Default")
      (node (ref "Q26") (pin "GATE") (pinfunction "P$3_GATE") (pintype "bidirectional"))
      (node (ref "R47") (pin "2") (pinfunction "2_2") (pintype "passive"))
      (node (ref "R48") (pin "1") (pinfunction "1_1") (pintype "passive"))
    )
    (net (code "140") (name "Net-(Q27-P$3)") (class "Default")
      (node (ref "Q27") (pin "GATE") (pinfunction "P$3_GATE") (pintype "bidirectional"))
      (node (ref "R49") (pin "2") (pinfunction "2_2") (pintype "passive"))
      (node (ref "R50") (pin "1") (pinfunction "1_1") (pintype "passive"))
    )
    (net (code "141") (name "Net-(Q28-P$3)") (class "Default")
      (node (ref "Q28") (pin "GATE") (pinfunction "P$3_GATE") (pintype "bidirectional"))
      (node (ref "R51") (pin "2") (pinfunction "2_2") (pintype "passive"))
      (node (ref "R54") (pin "1") (pinfunction "1_1") (pintype "passive"))
    )
    (net (code "142") (name "Net-(Q29-P$3)") (class "Default")
      (node (ref "Q29") (pin "GATE") (pinfunction "P$3_GATE") (pintype "bidirectional"))
      (node (ref "R52") (pin "2") (pinfunction "2_2") (pintype "passive"))
      (node (ref "R55") (pin "1") (pinfunction "1_1") (pintype "passive"))
    )
    (net (code "143") (name "Net-(Q30-P$3)") (class "Default")
      (node (ref "Q30") (pin "GATE") (pinfunction "P$3_GATE") (pintype "bidirectional"))
      (node (ref "R53") (pin "2") (pinfunction "2_2") (pintype "passive"))
      (node (ref "R56") (pin "1") (pinfunction "1_1") (pintype "passive"))
    )
    (net (code "144") (name "Net-(R2-Pad2)") (class "Default")
      (node (ref "R2") (pin "2") (pinfunction "2_2") (pintype "passive"))
      (node (ref "SPI_HEADER") (pin "1") (pinfunction "1_1") (pintype "passive"))
    )
    (net (code "145") (name "Net-(R3-Pad2)") (class "Default")
      (node (ref "R3") (pin "2") (pinfunction "2_2") (pintype "passive"))
      (node (ref "SPI_HEADER") (pin "2") (pinfunction "2_2") (pintype "passive"))
    )
    (net (code "146") (name "Net-(R4-Pad2)") (class "Default")
      (node (ref "R4") (pin "2") (pinfunction "2_2") (pintype "passive"))
      (node (ref "SPI_HEADER") (pin "3") (pinfunction "3_3") (pintype "passive"))
    )
    (net (code "147") (name "Net-(R5-Pad1)") (class "Default")
      (node (ref "R5") (pin "1") (pinfunction "1_1") (pintype "passive"))
      (node (ref "U$4") (pin "TDEAD") (pinfunction "TDEAD_TDEAD") (pintype "bidirectional"))
    )
    (net (code "148") (name "Net-(R6-Pad1)") (class "Default")
      (node (ref "R6") (pin "1") (pinfunction "1_1") (pintype "passive"))
      (node (ref "U$4") (pin "GHA") (pinfunction "GHA_GHA") (pintype "bidirectional"))
    )
    (net (code "149") (name "Net-(R8-Pad1)") (class "Default")
      (node (ref "R8") (pin "1") (pinfunction "1_1") (pintype "passive"))
      (node (ref "U$4") (pin "GHB") (pinfunction "GHB_GHB") (pintype "bidirectional"))
    )
    (net (code "150") (name "Net-(R10-Pad1)") (class "Default")
      (node (ref "R10") (pin "1") (pinfunction "1_1") (pintype "passive"))
      (node (ref "U$4") (pin "GHC") (pinfunction "GHC_GHC") (pintype "bidirectional"))
    )
    (net (code "151") (name "Net-(R12-Pad1)") (class "Default")
      (node (ref "R12") (pin "1") (pinfunction "1_1") (pintype "passive"))
      (node (ref "U$4") (pin "GLA") (pinfunction "GLA_GLA") (pintype "bidirectional"))
    )
    (net (code "152") (name "Net-(R13-Pad1)") (class "Default")
      (node (ref "R13") (pin "1") (pinfunction "1_1") (pintype "passive"))
      (node (ref "U$4") (pin "GLB") (pinfunction "GLB_GLB") (pintype "bidirectional"))
    )
    (net (code "153") (name "Net-(R14-Pad1)") (class "Default")
      (node (ref "R14") (pin "1") (pinfunction "1_1") (pintype "passive"))
      (node (ref "U$4") (pin "GLC") (pinfunction "GLC_GLC") (pintype "bidirectional"))
    )
    (net (code "154") (name "Net-(R18-Pad1)") (class "Default")
      (node (ref "R18") (pin "1") (pinfunction "1_1") (pintype "passive"))
      (node (ref "U$1") (pin "TDEAD") (pinfunction "TDEAD_TDEAD") (pintype "bidirectional"))
    )
    (net (code "155") (name "Net-(R19-Pad1)") (class "Default")
      (node (ref "R19") (pin "1") (pinfunction "1_1") (pintype "passive"))
      (node (ref "U$1") (pin "GHA") (pinfunction "GHA_GHA") (pintype "bidirectional"))
    )
    (net (code "156") (name "Net-(R21-Pad1)") (class "Default")
      (node (ref "R21") (pin "1") (pinfunction "1_1") (pintype "passive"))
      (node (ref "U$1") (pin "GHB") (pinfunction "GHB_GHB") (pintype "bidirectional"))
    )
    (net (code "157") (name "Net-(R23-Pad1)") (class "Default")
      (node (ref "R23") (pin "1") (pinfunction "1_1") (pintype "passive"))
      (node (ref "U$1") (pin "GHC") (pinfunction "GHC_GHC") (pintype "bidirectional"))
    )
    (net (code "158") (name "Net-(R25-Pad1)") (class "Default")
      (node (ref "R25") (pin "1") (pinfunction "1_1") (pintype "passive"))
      (node (ref "U$1") (pin "GLA") (pinfunction "GLA_GLA") (pintype "bidirectional"))
    )
    (net (code "159") (name "Net-(R26-Pad1)") (class "Default")
      (node (ref "R26") (pin "1") (pinfunction "1_1") (pintype "passive"))
      (node (ref "U$1") (pin "GLB") (pinfunction "GLB_GLB") (pintype "bidirectional"))
    )
    (net (code "160") (name "Net-(R27-Pad1)") (class "Default")
      (node (ref "R27") (pin "1") (pinfunction "1_1") (pintype "passive"))
      (node (ref "U$1") (pin "GLC") (pinfunction "GLC_GLC") (pintype "bidirectional"))
    )
    (net (code "161") (name "Net-(R31-Pad1)") (class "Default")
      (node (ref "R31") (pin "1") (pinfunction "1_1") (pintype "passive"))
      (node (ref "U$2") (pin "TDEAD") (pinfunction "TDEAD_TDEAD") (pintype "bidirectional"))
    )
    (net (code "162") (name "Net-(R32-Pad1)") (class "Default")
      (node (ref "R32") (pin "1") (pinfunction "1_1") (pintype "passive"))
      (node (ref "U$2") (pin "GHA") (pinfunction "GHA_GHA") (pintype "bidirectional"))
    )
    (net (code "163") (name "Net-(R34-Pad1)") (class "Default")
      (node (ref "R34") (pin "1") (pinfunction "1_1") (pintype "passive"))
      (node (ref "U$2") (pin "GHB") (pinfunction "GHB_GHB") (pintype "bidirectional"))
    )
    (net (code "164") (name "Net-(R36-Pad1)") (class "Default")
      (node (ref "R36") (pin "1") (pinfunction "1_1") (pintype "passive"))
      (node (ref "U$2") (pin "GHC") (pinfunction "GHC_GHC") (pintype "bidirectional"))
    )
    (net (code "165") (name "Net-(R38-Pad1)") (class "Default")
      (node (ref "R38") (pin "1") (pinfunction "1_1") (pintype "passive"))
      (node (ref "U$2") (pin "GLA") (pinfunction "GLA_GLA") (pintype "bidirectional"))
    )
    (net (code "166") (name "Net-(R39-Pad1)") (class "Default")
      (node (ref "R39") (pin "1") (pinfunction "1_1") (pintype "passive"))
      (node (ref "U$2") (pin "GLB") (pinfunction "GLB_GLB") (pintype "bidirectional"))
    )
    (net (code "167") (name "Net-(R40-Pad1)") (class "Default")
      (node (ref "R40") (pin "1") (pinfunction "1_1") (pintype "passive"))
      (node (ref "U$2") (pin "GLC") (pinfunction "GLC_GLC") (pintype "bidirectional"))
    )
    (net (code "168") (name "Net-(R44-Pad1)") (class "Default")
      (node (ref "R44") (pin "1") (pinfunction "1_1") (pintype "passive"))
      (node (ref "U$3") (pin "TDEAD") (pinfunction "TDEAD_TDEAD") (pintype "bidirectional"))
    )
    (net (code "169") (name "Net-(R45-Pad1)") (class "Default")
      (node (ref "R45") (pin "1") (pinfunction "1_1") (pintype "passive"))
      (node (ref "U$3") (pin "GHA") (pinfunction "GHA_GHA") (pintype "bidirectional"))
    )
    (net (code "170") (name "Net-(R47-Pad1)") (class "Default")
      (node (ref "R47") (pin "1") (pinfunction "1_1") (pintype "passive"))
      (node (ref "U$3") (pin "GHB") (pinfunction "GHB_GHB") (pintype "bidirectional"))
    )
    (net (code "171") (name "Net-(R49-Pad1)") (class "Default")
      (node (ref "R49") (pin "1") (pinfunction "1_1") (pintype "passive"))
      (node (ref "U$3") (pin "GHC") (pinfunction "GHC_GHC") (pintype "bidirectional"))
    )
    (net (code "172") (name "Net-(R51-Pad1)") (class "Default")
      (node (ref "R51") (pin "1") (pinfunction "1_1") (pintype "passive"))
      (node (ref "U$3") (pin "GLA") (pinfunction "GLA_GLA") (pintype "bidirectional"))
    )
    (net (code "173") (name "Net-(R52-Pad1)") (class "Default")
      (node (ref "R52") (pin "1") (pinfunction "1_1") (pintype "passive"))
      (node (ref "U$3") (pin "GLB") (pinfunction "GLB_GLB") (pintype "bidirectional"))
    )
    (net (code "174") (name "Net-(R53-Pad1)") (class "Default")
      (node (ref "R53") (pin "1") (pinfunction "1_1") (pintype "passive"))
      (node (ref "U$3") (pin "GLC") (pinfunction "GLC_GLC") (pintype "bidirectional"))
    )
    (net (code "175") (name "Net-(R78-Pad1)") (class "Default")
      (node (ref "R78") (pin "1") (pinfunction "1_1") (pintype "passive"))
      (node (ref "U$4") (pin "DIR") (pinfunction "DIR_DIR") (pintype "bidirectional"))
    )
    (net (code "176") (name "Net-(R79-Pad1)") (class "Default")
      (node (ref "R79") (pin "1") (pinfunction "1_1") (pintype "passive"))
      (node (ref "U$4") (pin "BRAKEN") (pinfunction "BRAKEN_BRAKEN") (pintype "bidirectional"))
    )
    (net (code "177") (name "Net-(R81-Pad1)") (class "Default")
      (node (ref "R81") (pin "1") (pinfunction "1_1") (pintype "passive"))
      (node (ref "U$1") (pin "DIR") (pinfunction "DIR_DIR") (pintype "bidirectional"))
    )
    (net (code "178") (name "Net-(R82-Pad1)") (class "Default")
      (node (ref "R82") (pin "1") (pinfunction "1_1") (pintype "passive"))
      (node (ref "U$1") (pin "BRAKEN") (pinfunction "BRAKEN_BRAKEN") (pintype "bidirectional"))
    )
    (net (code "179") (name "Net-(R84-Pad1)") (class "Default")
      (node (ref "R84") (pin "1") (pinfunction "1_1") (pintype "passive"))
      (node (ref "U$3") (pin "DIR") (pinfunction "DIR_DIR") (pintype "bidirectional"))
    )
    (net (code "180") (name "Net-(R85-Pad1)") (class "Default")
      (node (ref "R85") (pin "1") (pinfunction "1_1") (pintype "passive"))
      (node (ref "U$3") (pin "BRAKEN") (pinfunction "BRAKEN_BRAKEN") (pintype "bidirectional"))
    )
    (net (code "181") (name "Net-(R87-Pad1)") (class "Default")
      (node (ref "R87") (pin "1") (pinfunction "1_1") (pintype "passive"))
      (node (ref "U$2") (pin "DIR") (pinfunction "DIR_DIR") (pintype "bidirectional"))
    )
    (net (code "182") (name "Net-(R88-Pad1)") (class "Default")
      (node (ref "R88") (pin "1") (pinfunction "1_1") (pintype "passive"))
      (node (ref "U$2") (pin "BRAKEN") (pinfunction "BRAKEN_BRAKEN") (pintype "bidirectional"))
    )
    (net (code "183") (name "Net-(U2-AREF)") (class "Default")
      (node (ref "C33") (pin "2") (pinfunction "2_2") (pintype "passive"))
      (node (ref "U2") (pin "62") (pinfunction "AREF_62") (pintype "input"))
    )
    (net (code "184") (name "Net-(U2-AVCC)") (class "Default")
      (node (ref "C40") (pin "2") (pinfunction "2_2") (pintype "passive"))
      (node (ref "R97") (pin "1") (pinfunction "1_1") (pintype "passive"))
      (node (ref "U2") (pin "64") (pinfunction "AVCC_64") (pintype "power_in"))
    )
    (net (code "185") (name "unconnected-(JP1-Pad3)") (class "Default")
      (node (ref "JP1") (pin "3") (pinfunction "3_3") (pintype "passive"))
    )
    (net (code "186") (name "unconnected-(SPARE_HEADER-Pad1)") (class "Default")
      (node (ref "SPARE_HEADER") (pin "1") (pinfunction "1_1") (pintype "passive"))
    )
    (net (code "187") (name "unconnected-(SPARE_HEADER-Pad2)") (class "Default")
      (node (ref "SPARE_HEADER") (pin "2") (pinfunction "2_2") (pintype "passive"))
    )
    (net (code "188") (name "unconnected-(SPARE_HEADER-Pad3)") (class "Default")
      (node (ref "SPARE_HEADER") (pin "3") (pinfunction "3_3") (pintype "passive"))
    )
    (net (code "189") (name "unconnected-(SPARE_HEADER-Pad4)") (class "Default")
      (node (ref "SPARE_HEADER") (pin "4") (pinfunction "4_4") (pintype "passive"))
    )
    (net (code "190") (name "unconnected-(SPARE_HEADER-Pad5)") (class "Default")
      (node (ref "SPARE_HEADER") (pin "5") (pinfunction "5_5") (pintype "passive"))
    )
    (net (code "191") (name "unconnected-(SPARE_HEADER-Pad6)") (class "Default")
      (node (ref "SPARE_HEADER") (pin "6") (pinfunction "6_6") (pintype "passive"))
    )
    (net (code "192") (name "unconnected-(SPARE_HEADER-Pad7)") (class "Default")
      (node (ref "SPARE_HEADER") (pin "7") (pinfunction "7_7") (pintype "passive"))
    )
    (net (code "193") (name "unconnected-(SPARE_HEADER-Pad8)") (class "Default")
      (node (ref "SPARE_HEADER") (pin "8") (pinfunction "8_8") (pintype "passive"))
    )
    (net (code "194") (name "unconnected-(SPARE_HEADER-Pad9)") (class "Default")
      (node (ref "SPARE_HEADER") (pin "9") (pinfunction "9_9") (pintype "passive"))
    )
    (net (code "195") (name "unconnected-(SPARE_HEADER-Pad10)") (class "Default")
      (node (ref "SPARE_HEADER") (pin "10") (pinfunction "10_10") (pintype "passive"))
    )
    (net (code "196") (name "unconnected-(SPI_HEADER-Pad9)") (class "Default")
      (node (ref "SPI_HEADER") (pin "9") (pinfunction "9_9") (pintype "passive"))
    )
    (net (code "197") (name "unconnected-(SPI_HEADER-Pad10)") (class "Default")
      (node (ref "SPI_HEADER") (pin "10") (pinfunction "10_10") (pintype "passive"))
    )
    (net (code "198") (name "unconnected-(U2-(TOSC1)_XTAL1-Pad24)") (class "Default")
      (node (ref "U2") (pin "24") (pinfunction "(TOSC1)_XTAL1_24") (pintype "input"))
    )
    (net (code "199") (name "unconnected-(U2-(TOSC2)_XTAL2-Pad23)") (class "Default")
      (node (ref "U2") (pin "23") (pinfunction "(TOSC2)_XTAL2_23") (pintype "output"))
    )
    (net (code "200") (name "unconnected-(U2-DNC-Pad1)") (class "Default")
      (node (ref "U2") (pin "1") (pinfunction "DNC_1") (pintype "no_connect"))
    )
    (net (code "201") (name "unconnected-(U2-PA0-Pad51)") (class "Default")
      (node (ref "U2") (pin "51") (pinfunction "PA0_51") (pintype "bidirectional"))
    )
    (net (code "202") (name "unconnected-(U2-PA1-Pad50)") (class "Default")
      (node (ref "U2") (pin "50") (pinfunction "PA1_50") (pintype "bidirectional"))
    )
    (net (code "203") (name "unconnected-(U2-PA2-Pad49)") (class "Default")
      (node (ref "U2") (pin "49") (pinfunction "PA2_49") (pintype "bidirectional"))
    )
    (net (code "204") (name "unconnected-(U2-PA3-Pad48)") (class "Default")
      (node (ref "U2") (pin "48") (pinfunction "PA3_48") (pintype "bidirectional"))
    )
    (net (code "205") (name "unconnected-(U2-PA4-Pad47)") (class "Default")
      (node (ref "U2") (pin "47") (pinfunction "PA4_47") (pintype "bidirectional"))
    )
    (net (code "206") (name "unconnected-(U2-PA5-Pad46)") (class "Default")
      (node (ref "U2") (pin "46") (pinfunction "PA5_46") (pintype "bidirectional"))
    )
    (net (code "207") (name "unconnected-(U2-PA6-Pad45)") (class "Default")
      (node (ref "U2") (pin "45") (pinfunction "PA6_45") (pintype "bidirectional"))
    )
    (net (code "208") (name "unconnected-(U2-PA7-Pad44)") (class "Default")
      (node (ref "U2") (pin "44") (pinfunction "PA7_44") (pintype "bidirectional"))
    )
    (net (code "209") (name "unconnected-(U2-PC4-Pad39)") (class "Default")
      (node (ref "U2") (pin "39") (pinfunction "PC4_39") (pintype "bidirectional"))
    )
    (net (code "210") (name "unconnected-(U2-PC5-Pad40)") (class "Default")
      (node (ref "U2") (pin "40") (pinfunction "PC5_40") (pintype "bidirectional"))
    )
    (net (code "211") (name "unconnected-(U2-PC6-Pad41)") (class "Default")
      (node (ref "U2") (pin "41") (pinfunction "PC6_41") (pintype "bidirectional"))
    )
    (net (code "212") (name "unconnected-(U2-PC7-Pad42)") (class "Default")
      (node (ref "U2") (pin "42") (pinfunction "PC7_42") (pintype "bidirectional"))
    )
    (net (code "213") (name "unconnected-(U2-PD5-Pad30)") (class "Default")
      (node (ref "U2") (pin "30") (pinfunction "PD5_30") (pintype "bidirectional"))
    )
    (net (code "214") (name "unconnected-(U2-PD6-Pad31)") (class "Default")
      (node (ref "U2") (pin "31") (pinfunction "PD6_31") (pintype "bidirectional"))
    )
    (net (code "215") (name "unconnected-(U2-PD7-Pad32)") (class "Default")
      (node (ref "U2") (pin "32") (pinfunction "PD7_32") (pintype "bidirectional"))
    )
    (net (code "216") (name "unconnected-(U2-PG4-Pad19)") (class "Default")
      (node (ref "U2") (pin "19") (pinfunction "PG4_19") (pintype "bidirectional"))
    )
  )
)
